# 03_-_28PINS_SCHEMATIC.net
KiCad netlist of a schematic drawn in Altium Designer
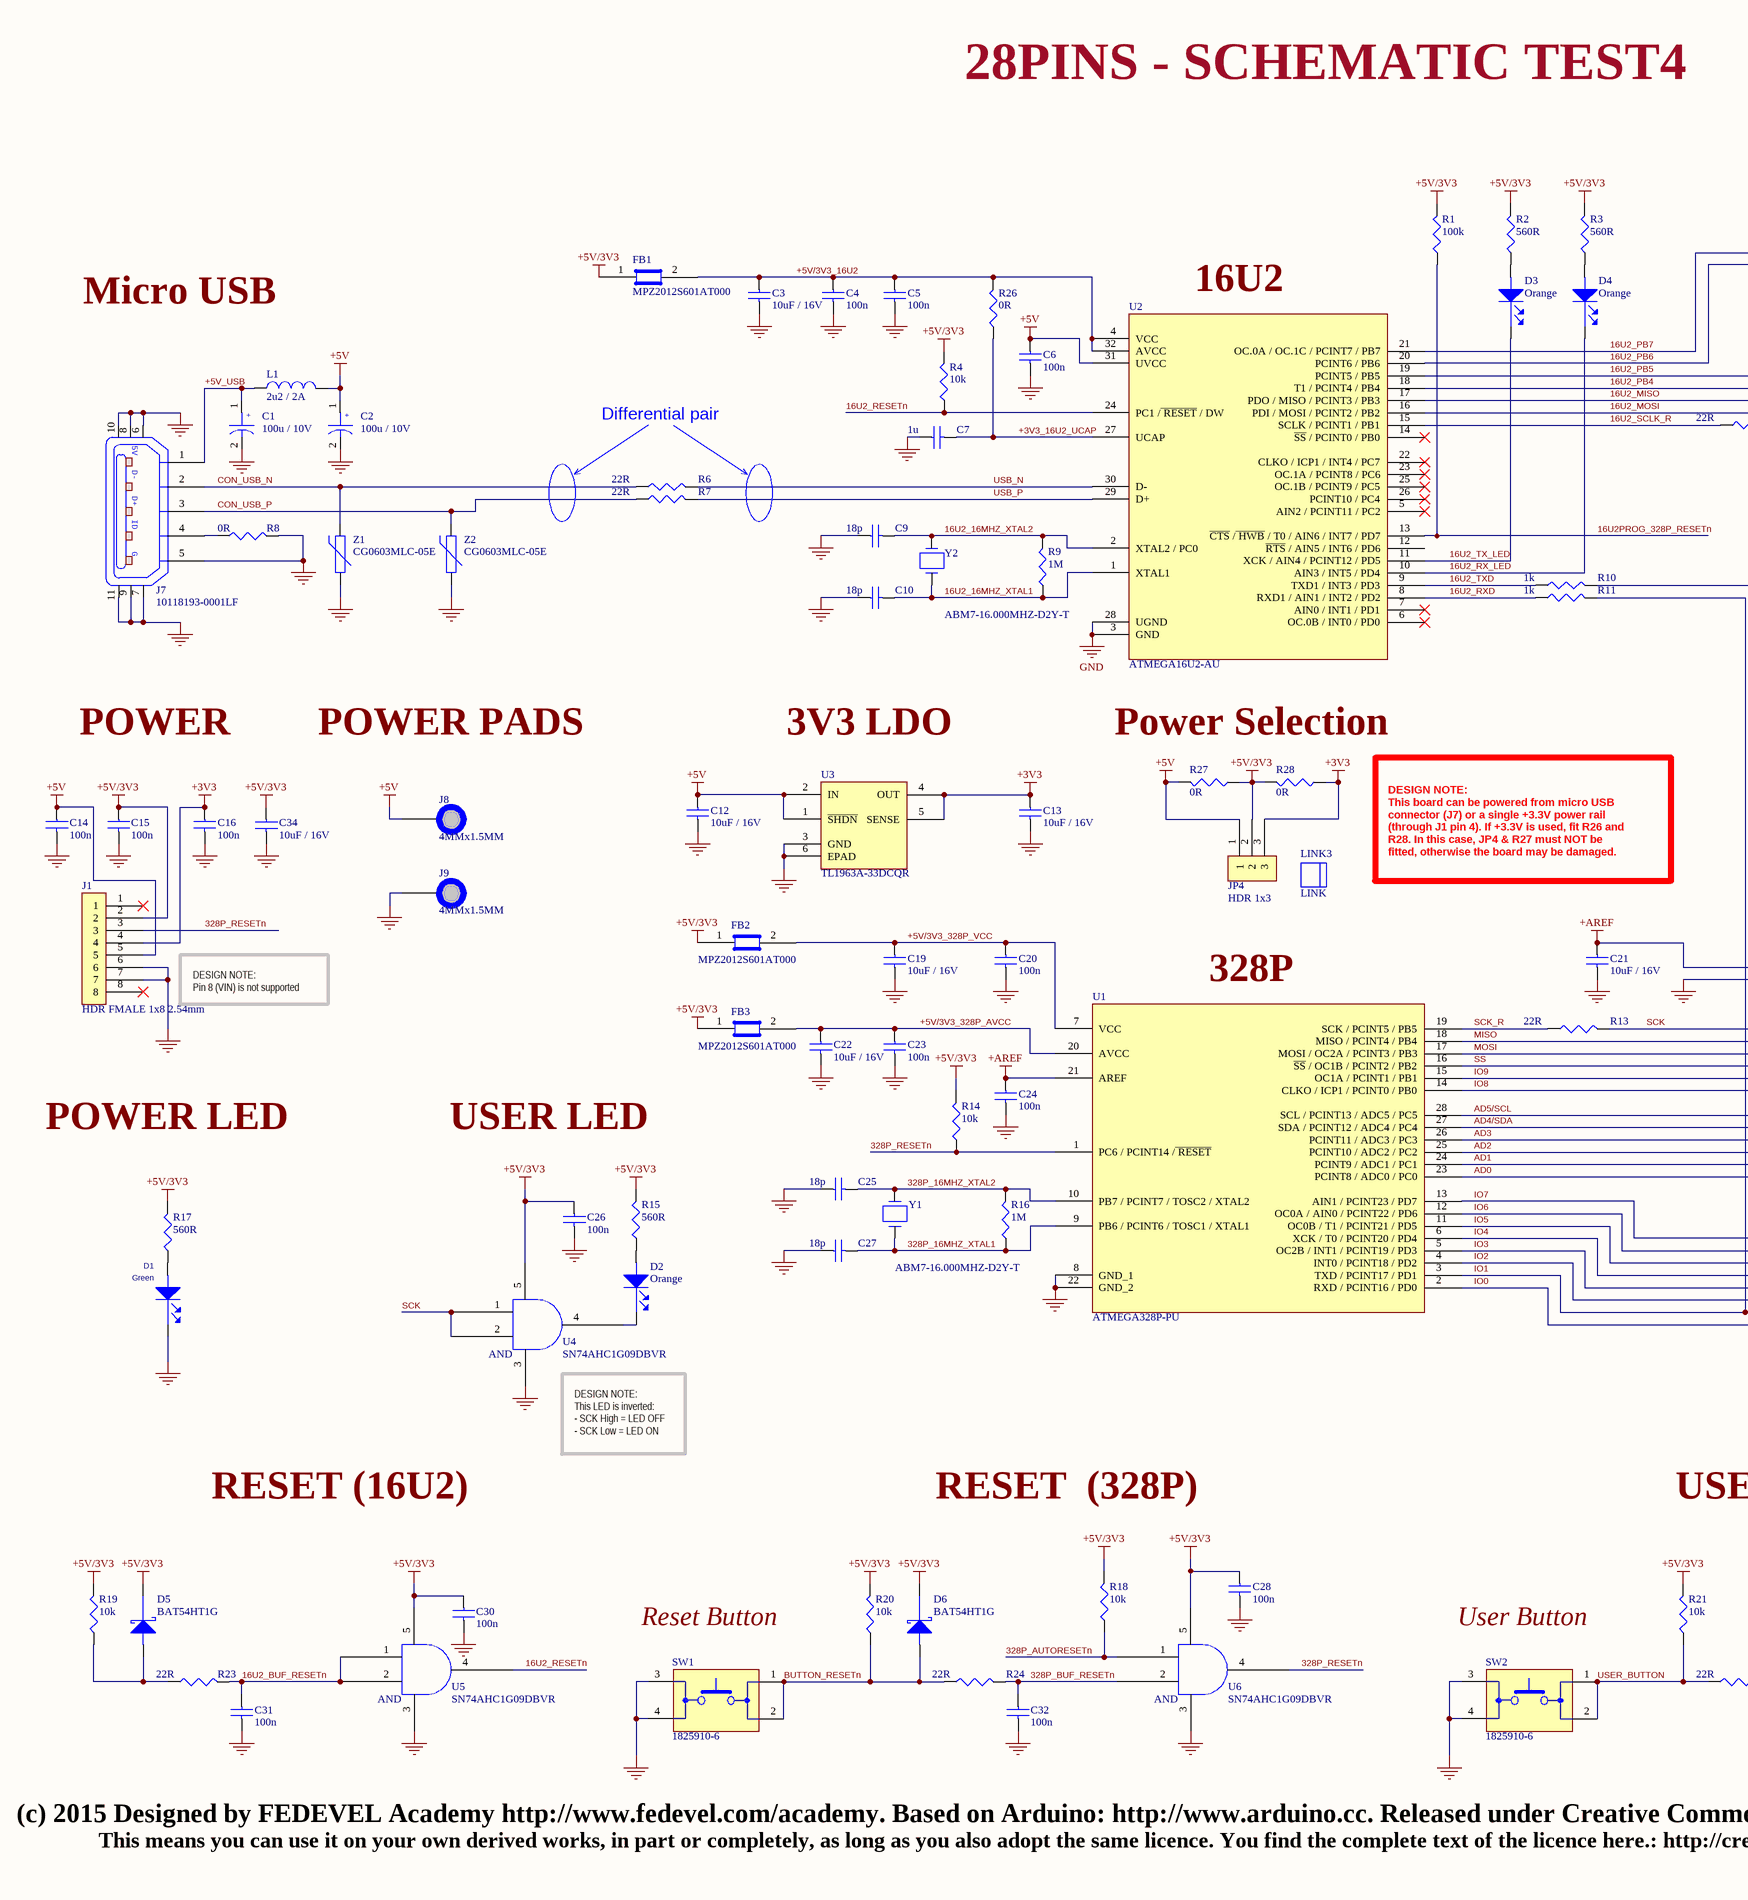
[diagram p0: [03] - 28PINS SCHEMATIC.SchDoc, left]
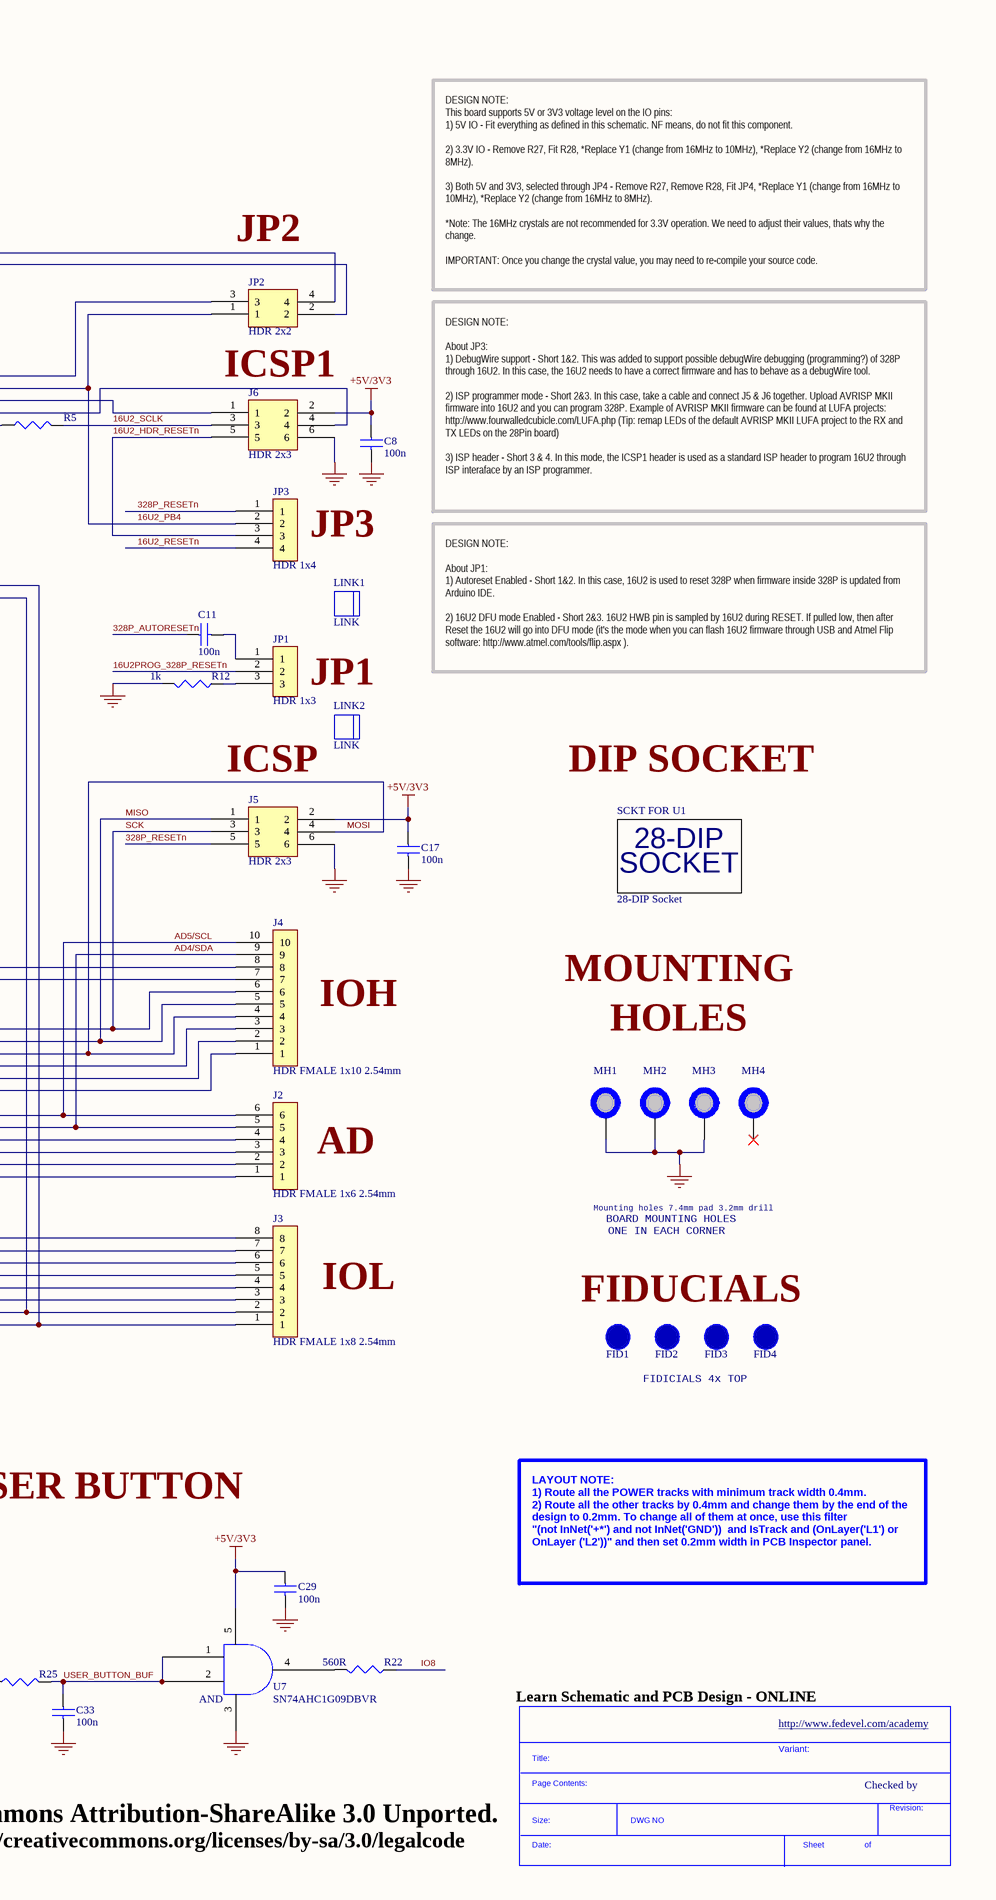
[diagram p1: [03] - 28PINS SCHEMATIC.SchDoc, right]

(export (version "E")
  (design (tool "Eeschema 10.0.6"))
  (components
    (comp (ref "*") (value "SDTitleBlock") (libsource (lib "*") (part "SDTitleBlock")))
    (comp (ref "C1")
      (value "100u / 10V")
      (footprint "C_ALU_C_SIZE")
      (description "CAP ALUM 100UF 10V 20% SMD")
      (fields
        (field (name "MANUFACTURER") "Panasonic Electronic Components")
        (field (name "MANUFACTURER PART NUMBER") "EEE-1AA101WR")
        (field (name ".CREATOR") "MM")
        (field (name ".CHECKED PCB") "RF")
        (field (name ".CHECKED SCH") "RF")
      )
      (libsource (lib "Integrated_Library_FEDEVEL_APR_2015") (part "EEE-1AA101WR"))
    )
    (comp (ref "C2")
      (value "100u / 10V")
      (footprint "C_ALU_C_SIZE")
      (description "CAP ALUM 100UF 10V 20% SMD")
      (fields
        (field (name "MANUFACTURER") "Panasonic Electronic Components")
        (field (name "MANUFACTURER PART NUMBER") "EEE-1AA101WR")
        (field (name ".CREATOR") "MM")
        (field (name ".CHECKED PCB") "RF")
        (field (name ".CHECKED SCH") "RF")
      )
      (libsource (lib "Integrated_Library_FEDEVEL_APR_2015") (part "EEE-1AA101WR"))
    )
    (comp (ref "C3")
      (value "10uF / 16V")
      (footprint "C0805")
      (description "CAP CER 10UF 16V 20% X5R 0805")
      (fields
        (field (name "MANUFACTURER") "TDK Corporation")
        (field (name "MANUFACTURER PART NUMBER") "C2012X5R1C106M/1.25")
      )
      (libsource (lib "Integrated_Library_FEDEVEL_APR_2015") (part "C2012X5R1C106M"))
    )
    (comp (ref "C4")
      (value "100n")
      (footprint "C0805")
      (description "CAP CER 0.1UF 50V 10% X7R 0805")
      (fields
        (field (name "MANUFACTURER") "TDK Corporation")
        (field (name "MANUFACTURER PART NUMBER") "C2012X7R1H104K085AA")
        (field (name ".CREATOR") "MM")
        (field (name ".CHECKED PCB") "RF")
        (field (name ".CHECKED SCH") "RF")
      )
      (libsource (lib "Integrated_Library_FEDEVEL_APR_2015") (part "C2012X7R1H104K085AA"))
    )
    (comp (ref "C5")
      (value "100n")
      (footprint "C0805")
      (description "CAP CER 0.1UF 50V 10% X7R 0805")
      (fields
        (field (name "MANUFACTURER") "TDK Corporation")
        (field (name "MANUFACTURER PART NUMBER") "C2012X7R1H104K085AA")
        (field (name ".CREATOR") "MM")
        (field (name ".CHECKED PCB") "RF")
        (field (name ".CHECKED SCH") "RF")
      )
      (libsource (lib "Integrated_Library_FEDEVEL_APR_2015") (part "C2012X7R1H104K085AA"))
    )
    (comp (ref "C6")
      (value "100n")
      (footprint "C0805")
      (description "CAP CER 0.1UF 50V 10% X7R 0805")
      (fields
        (field (name "MANUFACTURER") "TDK Corporation")
        (field (name "MANUFACTURER PART NUMBER") "C2012X7R1H104K085AA")
        (field (name ".CREATOR") "MM")
        (field (name ".CHECKED PCB") "RF")
        (field (name ".CHECKED SCH") "RF")
      )
      (libsource (lib "Integrated_Library_FEDEVEL_APR_2015") (part "C2012X7R1H104K085AA"))
    )
    (comp (ref "C7")
      (value "1u")
      (footprint "C0805")
      (description "CAP CER 1UF 25V 10% X5R 0805")
      (fields
        (field (name "MANUFACTURER") "TDK Corporation")
        (field (name "MANUFACTURER PART NUMBER") "C2012X5R1E105K125AA")
        (field (name ".CREATOR") "MM")
        (field (name ".CHECKED PCB") "RF")
        (field (name ".CHECKED SCH") "RF")
      )
      (libsource (lib "Integrated_Library_FEDEVEL_APR_2015") (part "C2012X5R1E105K125AA"))
    )
    (comp (ref "C8")
      (value "100n")
      (footprint "C0805")
      (description "CAP CER 0.1UF 50V 10% X7R 0805")
      (fields
        (field (name "MANUFACTURER") "TDK Corporation")
        (field (name "MANUFACTURER PART NUMBER") "C2012X7R1H104K085AA")
        (field (name ".CREATOR") "MM")
        (field (name ".CHECKED PCB") "RF")
        (field (name ".CHECKED SCH") "RF")
      )
      (libsource (lib "Integrated_Library_FEDEVEL_APR_2015") (part "C2012X7R1H104K085AA"))
    )
    (comp (ref "C9")
      (value "18p")
      (footprint "C0805")
      (description "CAP CER 18PF 50V 5% NP0 0805")
      (fields
        (field (name "MANUFACTURER") "Kemet")
        (field (name "MANUFACTURER PART NUMBER") "C0805C180J5GACTU")
        (field (name ".CREATOR") "MM")
        (field (name ".CHECKED PCB") "RF")
        (field (name ".CHECKED SCH") "RF")
      )
      (libsource (lib "Integrated_Library_FEDEVEL_APR_2015") (part "C0805C180J5GACTU"))
    )
    (comp (ref "C10")
      (value "18p")
      (footprint "C0805")
      (description "CAP CER 18PF 50V 5% NP0 0805")
      (fields
        (field (name "MANUFACTURER") "Kemet")
        (field (name "MANUFACTURER PART NUMBER") "C0805C180J5GACTU")
        (field (name ".CREATOR") "MM")
        (field (name ".CHECKED PCB") "RF")
        (field (name ".CHECKED SCH") "RF")
      )
      (libsource (lib "Integrated_Library_FEDEVEL_APR_2015") (part "C0805C180J5GACTU"))
    )
    (comp (ref "C11")
      (value "100n")
      (footprint "C0805")
      (description "CAP CER 0.1UF 50V 10% X7R 0805")
      (fields
        (field (name "MANUFACTURER") "TDK Corporation")
        (field (name "MANUFACTURER PART NUMBER") "C2012X7R1H104K085AA")
        (field (name ".CREATOR") "MM")
        (field (name ".CHECKED PCB") "RF")
        (field (name ".CHECKED SCH") "RF")
      )
      (libsource (lib "Integrated_Library_FEDEVEL_APR_2015") (part "C2012X7R1H104K085AA"))
    )
    (comp (ref "C12")
      (value "10uF / 16V")
      (footprint "C0805")
      (description "CAP CER 10UF 16V 20% X5R 0805")
      (fields
        (field (name "MANUFACTURER") "TDK Corporation")
        (field (name "MANUFACTURER PART NUMBER") "C2012X5R1C106M/1.25")
      )
      (libsource (lib "Integrated_Library_FEDEVEL_APR_2015") (part "C2012X5R1C106M"))
    )
    (comp (ref "C13")
      (value "10uF / 16V")
      (footprint "C0805")
      (description "CAP CER 10UF 16V 20% X5R 0805")
      (fields
        (field (name "MANUFACTURER") "TDK Corporation")
        (field (name "MANUFACTURER PART NUMBER") "C2012X5R1C106M/1.25")
      )
      (libsource (lib "Integrated_Library_FEDEVEL_APR_2015") (part "C2012X5R1C106M"))
    )
    (comp (ref "C14")
      (value "100n")
      (footprint "C0805")
      (description "CAP CER 0.1UF 50V 10% X7R 0805")
      (fields
        (field (name "MANUFACTURER") "TDK Corporation")
        (field (name "MANUFACTURER PART NUMBER") "C2012X7R1H104K085AA")
        (field (name ".CREATOR") "MM")
        (field (name ".CHECKED PCB") "RF")
        (field (name ".CHECKED SCH") "RF")
      )
      (libsource (lib "Integrated_Library_FEDEVEL_APR_2015") (part "C2012X7R1H104K085AA"))
    )
    (comp (ref "C15")
      (value "100n")
      (footprint "C0805")
      (description "CAP CER 0.1UF 50V 10% X7R 0805")
      (fields
        (field (name "MANUFACTURER") "TDK Corporation")
        (field (name "MANUFACTURER PART NUMBER") "C2012X7R1H104K085AA")
        (field (name ".CREATOR") "MM")
        (field (name ".CHECKED PCB") "RF")
        (field (name ".CHECKED SCH") "RF")
      )
      (libsource (lib "Integrated_Library_FEDEVEL_APR_2015") (part "C2012X7R1H104K085AA"))
    )
    (comp (ref "C16")
      (value "100n")
      (footprint "C0805")
      (description "CAP CER 0.1UF 50V 10% X7R 0805")
      (fields
        (field (name "MANUFACTURER") "TDK Corporation")
        (field (name "MANUFACTURER PART NUMBER") "C2012X7R1H104K085AA")
        (field (name ".CREATOR") "MM")
        (field (name ".CHECKED PCB") "RF")
        (field (name ".CHECKED SCH") "RF")
      )
      (libsource (lib "Integrated_Library_FEDEVEL_APR_2015") (part "C2012X7R1H104K085AA"))
    )
    (comp (ref "C17")
      (value "100n")
      (footprint "C0805")
      (description "CAP CER 0.1UF 50V 10% X7R 0805")
      (fields
        (field (name "MANUFACTURER") "TDK Corporation")
        (field (name "MANUFACTURER PART NUMBER") "C2012X7R1H104K085AA")
        (field (name ".CREATOR") "MM")
        (field (name ".CHECKED PCB") "RF")
        (field (name ".CHECKED SCH") "RF")
      )
      (libsource (lib "Integrated_Library_FEDEVEL_APR_2015") (part "C2012X7R1H104K085AA"))
    )
    (comp (ref "C19")
      (value "10uF / 16V")
      (footprint "C0805")
      (description "CAP CER 10UF 16V 20% X5R 0805")
      (fields
        (field (name "MANUFACTURER") "TDK Corporation")
        (field (name "MANUFACTURER PART NUMBER") "C2012X5R1C106M/1.25")
      )
      (libsource (lib "Integrated_Library_FEDEVEL_APR_2015") (part "C2012X5R1C106M"))
    )
    (comp (ref "C20")
      (value "100n")
      (footprint "C0805")
      (description "CAP CER 0.1UF 50V 10% X7R 0805")
      (fields
        (field (name "MANUFACTURER") "TDK Corporation")
        (field (name "MANUFACTURER PART NUMBER") "C2012X7R1H104K085AA")
        (field (name ".CREATOR") "MM")
        (field (name ".CHECKED PCB") "RF")
        (field (name ".CHECKED SCH") "RF")
      )
      (libsource (lib "Integrated_Library_FEDEVEL_APR_2015") (part "C2012X7R1H104K085AA"))
    )
    (comp (ref "C21")
      (value "10uF / 16V")
      (footprint "C0805")
      (description "CAP CER 10UF 16V 20% X5R 0805")
      (fields
        (field (name "MANUFACTURER") "TDK Corporation")
        (field (name "MANUFACTURER PART NUMBER") "C2012X5R1C106M/1.25")
      )
      (libsource (lib "Integrated_Library_FEDEVEL_APR_2015") (part "C2012X5R1C106M"))
    )
    (comp (ref "C22")
      (value "10uF / 16V")
      (footprint "C0805")
      (description "CAP CER 10UF 16V 20% X5R 0805")
      (fields
        (field (name "MANUFACTURER") "TDK Corporation")
        (field (name "MANUFACTURER PART NUMBER") "C2012X5R1C106M/1.25")
      )
      (libsource (lib "Integrated_Library_FEDEVEL_APR_2015") (part "C2012X5R1C106M"))
    )
    (comp (ref "C23")
      (value "100n")
      (footprint "C0805")
      (description "CAP CER 0.1UF 50V 10% X7R 0805")
      (fields
        (field (name "MANUFACTURER") "TDK Corporation")
        (field (name "MANUFACTURER PART NUMBER") "C2012X7R1H104K085AA")
        (field (name ".CREATOR") "MM")
        (field (name ".CHECKED PCB") "RF")
        (field (name ".CHECKED SCH") "RF")
      )
      (libsource (lib "Integrated_Library_FEDEVEL_APR_2015") (part "C2012X7R1H104K085AA"))
    )
    (comp (ref "C24")
      (value "100n")
      (footprint "C0805")
      (description "CAP CER 0.1UF 50V 10% X7R 0805")
      (fields
        (field (name "MANUFACTURER") "TDK Corporation")
        (field (name "MANUFACTURER PART NUMBER") "C2012X7R1H104K085AA")
        (field (name ".CREATOR") "MM")
        (field (name ".CHECKED PCB") "RF")
        (field (name ".CHECKED SCH") "RF")
      )
      (libsource (lib "Integrated_Library_FEDEVEL_APR_2015") (part "C2012X7R1H104K085AA"))
    )
    (comp (ref "C25")
      (value "18p")
      (footprint "C0805")
      (description "CAP CER 18PF 50V 5% NP0 0805")
      (fields
        (field (name "MANUFACTURER") "Kemet")
        (field (name "MANUFACTURER PART NUMBER") "C0805C180J5GACTU")
        (field (name ".CREATOR") "MM")
        (field (name ".CHECKED PCB") "RF")
        (field (name ".CHECKED SCH") "RF")
      )
      (libsource (lib "Integrated_Library_FEDEVEL_APR_2015") (part "C0805C180J5GACTU"))
    )
    (comp (ref "C26")
      (value "100n")
      (footprint "C0805")
      (description "CAP CER 0.1UF 50V 10% X7R 0805")
      (fields
        (field (name "MANUFACTURER") "TDK Corporation")
        (field (name "MANUFACTURER PART NUMBER") "C2012X7R1H104K085AA")
        (field (name ".CREATOR") "MM")
        (field (name ".CHECKED PCB") "RF")
        (field (name ".CHECKED SCH") "RF")
      )
      (libsource (lib "Integrated_Library_FEDEVEL_APR_2015") (part "C2012X7R1H104K085AA"))
    )
    (comp (ref "C27")
      (value "18p")
      (footprint "C0805")
      (description "CAP CER 18PF 50V 5% NP0 0805")
      (fields
        (field (name "MANUFACTURER") "Kemet")
        (field (name "MANUFACTURER PART NUMBER") "C0805C180J5GACTU")
        (field (name ".CREATOR") "MM")
        (field (name ".CHECKED PCB") "RF")
        (field (name ".CHECKED SCH") "RF")
      )
      (libsource (lib "Integrated_Library_FEDEVEL_APR_2015") (part "C0805C180J5GACTU"))
    )
    (comp (ref "C28")
      (value "100n")
      (footprint "C0805")
      (description "CAP CER 0.1UF 50V 10% X7R 0805")
      (fields
        (field (name "MANUFACTURER") "TDK Corporation")
        (field (name "MANUFACTURER PART NUMBER") "C2012X7R1H104K085AA")
        (field (name ".CREATOR") "MM")
        (field (name ".CHECKED PCB") "RF")
        (field (name ".CHECKED SCH") "RF")
      )
      (libsource (lib "Integrated_Library_FEDEVEL_APR_2015") (part "C2012X7R1H104K085AA"))
    )
    (comp (ref "C29")
      (value "100n")
      (footprint "C0805")
      (description "CAP CER 0.1UF 50V 10% X7R 0805")
      (fields
        (field (name "MANUFACTURER") "TDK Corporation")
        (field (name "MANUFACTURER PART NUMBER") "C2012X7R1H104K085AA")
        (field (name ".CREATOR") "MM")
        (field (name ".CHECKED PCB") "RF")
        (field (name ".CHECKED SCH") "RF")
      )
      (libsource (lib "Integrated_Library_FEDEVEL_APR_2015") (part "C2012X7R1H104K085AA"))
    )
    (comp (ref "C30")
      (value "100n")
      (footprint "C0805")
      (description "CAP CER 0.1UF 50V 10% X7R 0805")
      (fields
        (field (name "MANUFACTURER") "TDK Corporation")
        (field (name "MANUFACTURER PART NUMBER") "C2012X7R1H104K085AA")
        (field (name ".CREATOR") "MM")
        (field (name ".CHECKED PCB") "RF")
        (field (name ".CHECKED SCH") "RF")
      )
      (libsource (lib "Integrated_Library_FEDEVEL_APR_2015") (part "C2012X7R1H104K085AA"))
    )
    (comp (ref "C31")
      (value "100n")
      (footprint "C0805")
      (description "CAP CER 0.1UF 50V 10% X7R 0805")
      (fields
        (field (name "MANUFACTURER") "TDK Corporation")
        (field (name "MANUFACTURER PART NUMBER") "C2012X7R1H104K085AA")
        (field (name ".CREATOR") "MM")
        (field (name ".CHECKED PCB") "RF")
        (field (name ".CHECKED SCH") "RF")
      )
      (libsource (lib "Integrated_Library_FEDEVEL_APR_2015") (part "C2012X7R1H104K085AA"))
    )
    (comp (ref "C32")
      (value "100n")
      (footprint "C0805")
      (description "CAP CER 0.1UF 50V 10% X7R 0805")
      (fields
        (field (name "MANUFACTURER") "TDK Corporation")
        (field (name "MANUFACTURER PART NUMBER") "C2012X7R1H104K085AA")
        (field (name ".CREATOR") "MM")
        (field (name ".CHECKED PCB") "RF")
        (field (name ".CHECKED SCH") "RF")
      )
      (libsource (lib "Integrated_Library_FEDEVEL_APR_2015") (part "C2012X7R1H104K085AA"))
    )
    (comp (ref "C33")
      (value "100n")
      (footprint "C0805")
      (description "CAP CER 0.1UF 50V 10% X7R 0805")
      (fields
        (field (name "MANUFACTURER") "TDK Corporation")
        (field (name "MANUFACTURER PART NUMBER") "C2012X7R1H104K085AA")
        (field (name ".CREATOR") "MM")
        (field (name ".CHECKED PCB") "RF")
        (field (name ".CHECKED SCH") "RF")
      )
      (libsource (lib "Integrated_Library_FEDEVEL_APR_2015") (part "C2012X7R1H104K085AA"))
    )
    (comp (ref "C34")
      (value "10uF / 16V")
      (footprint "C0805")
      (description "CAP CER 10UF 16V 20% X5R 0805")
      (fields
        (field (name "MANUFACTURER") "TDK Corporation")
        (field (name "MANUFACTURER PART NUMBER") "C2012X5R1C106M/1.25")
      )
      (libsource (lib "Integrated_Library_FEDEVEL_APR_2015") (part "C2012X5R1C106M"))
    )
    (comp (ref "D1")
      (value "Green")
      (footprint "LED_0603")
      (description "LED SMARTLED GREEN 570NM 0603")
      (fields
        (field (name "MANUFACTURER") "OSRAM Opto Semiconductors Inc")
        (field (name "MANUFACTURER PART NUMBER") "LG L29K-G2J1-24-Z")
      )
      (libsource (lib "Integrated_Library_FEDEVEL_APR_2015") (part "LG L29K-G2J1-24-Z"))
    )
    (comp (ref "D2")
      (value "Orange")
      (footprint "LED_0603")
      (description "LED SMARTLED ORANGE 606NM 0603")
      (fields
        (field (name "MANUFACTURER") "OSRAM Opto Semiconductors Inc")
        (field (name "MANUFACTURER PART NUMBER") "LO L29K-H2K1-24-Z")
      )
      (libsource (lib "Integrated_Library_FEDEVEL_APR_2015") (part "LO L29K-H2K1-24-Z"))
    )
    (comp (ref "D3")
      (value "Orange")
      (footprint "LED_0603")
      (description "LED SMARTLED ORANGE 606NM 0603")
      (fields
        (field (name "MANUFACTURER") "OSRAM Opto Semiconductors Inc")
        (field (name "MANUFACTURER PART NUMBER") "LO L29K-H2K1-24-Z")
      )
      (libsource (lib "Integrated_Library_FEDEVEL_APR_2015") (part "LO L29K-H2K1-24-Z"))
    )
    (comp (ref "D4")
      (value "Orange")
      (footprint "LED_0603")
      (description "LED SMARTLED ORANGE 606NM 0603")
      (fields
        (field (name "MANUFACTURER") "OSRAM Opto Semiconductors Inc")
        (field (name "MANUFACTURER PART NUMBER") "LO L29K-H2K1-24-Z")
      )
      (libsource (lib "Integrated_Library_FEDEVEL_APR_2015") (part "LO L29K-H2K1-24-Z"))
    )
    (comp (ref "D5")
      (value "BAT54HT1G")
      (footprint "SOD323")
      (description "DIODE SCHOTTKY 30V 0.2A SOD323")
      (fields (field (name "MANUFACTURER") "Fairchild Semiconductor") (field (name ".CREATOR") "MM"))
      (libsource (lib "Integrated_Library_FEDEVEL_APR_2015") (part "BAT54HT1G"))
    )
    (comp (ref "D6")
      (value "BAT54HT1G")
      (footprint "SOD323")
      (description "DIODE SCHOTTKY 30V 0.2A SOD323")
      (fields (field (name "MANUFACTURER") "Fairchild Semiconductor") (field (name ".CREATOR") "MM"))
      (libsource (lib "Integrated_Library_FEDEVEL_APR_2015") (part "BAT54HT1G"))
    )
    (comp (ref "FB1")
      (value "MPZ2012S601AT000")
      (footprint "C0805")
      (description "FERRITE CHIP BEAD 600 OHM SMD")
      (fields
        (field (name "MANUFACTURER") "TDK Corporation")
        (field (name ".CREATOR") "MM")
        (field (name ".CHECKED PCB") "RF")
        (field (name ".CHECKED SCH") "RF")
      )
      (libsource (lib "Integrated_Library_FEDEVEL_APR_2015") (part "MPZ2012S601AT000"))
    )
    (comp (ref "FB2")
      (value "MPZ2012S601AT000")
      (footprint "C0805")
      (description "FERRITE CHIP BEAD 600 OHM SMD")
      (fields
        (field (name "MANUFACTURER") "TDK Corporation")
        (field (name ".CREATOR") "MM")
        (field (name ".CHECKED PCB") "RF")
        (field (name ".CHECKED SCH") "RF")
      )
      (libsource (lib "Integrated_Library_FEDEVEL_APR_2015") (part "MPZ2012S601AT000"))
    )
    (comp (ref "FB3")
      (value "MPZ2012S601AT000")
      (footprint "C0805")
      (description "FERRITE CHIP BEAD 600 OHM SMD")
      (fields
        (field (name "MANUFACTURER") "TDK Corporation")
        (field (name ".CREATOR") "MM")
        (field (name ".CHECKED PCB") "RF")
        (field (name ".CHECKED SCH") "RF")
      )
      (libsource (lib "Integrated_Library_FEDEVEL_APR_2015") (part "MPZ2012S601AT000"))
    )
    (comp (ref "FID1")
      (value "FID_1MMC")
      (footprint "FID_40X120D")
      (description "Fiducial 40mil Diameter, 120mil Mask")
      (libsource (lib "Integrated_Library_FEDEVEL_APR_2015") (part "FID_1MMC"))
    )
    (comp (ref "FID2")
      (value "FID_1MMC")
      (footprint "FID_40X120D")
      (description "Fiducial 40mil Diameter, 120mil Mask")
      (libsource (lib "Integrated_Library_FEDEVEL_APR_2015") (part "FID_1MMC"))
    )
    (comp (ref "FID3")
      (value "FID_1MMC")
      (footprint "FID_40X120D")
      (description "Fiducial 40mil Diameter, 120mil Mask")
      (libsource (lib "Integrated_Library_FEDEVEL_APR_2015") (part "FID_1MMC"))
    )
    (comp (ref "FID4")
      (value "FID_1MMC")
      (footprint "FID_40X120D")
      (description "Fiducial 40mil Diameter, 120mil Mask")
      (libsource (lib "Integrated_Library_FEDEVEL_APR_2015") (part "FID_1MMC"))
    )
    (comp (ref "J1")
      (value "HDR FMALE 1x8 2.54mm")
      (footprint "Hdr_Female_1x8_2.54mm")
      (description "08-WAY SIL VERT SOCKET L/FREE")
      (fields
        (field (name "MANUFACTURER") "Harwin Inc")
        (field (name "MANUFACTURER PART NUMBER") "M20-7820842")
        (field (name ".CREATOR") "MM")
        (field (name ".CHECKED PCB") "RF")
        (field (name ".CHECKED SCH") "RF")
      )
      (libsource (lib "Integrated_Library_FEDEVEL_APR_2015") (part "M20-7820842"))
    )
    (comp (ref "J2")
      (value "HDR FMALE 1x6 2.54mm")
      (footprint "Hdr_Female_1x6_2.54mm")
      (description "06-WAY SIL VERT SOCKET L/FREE")
      (fields
        (field (name "MANUFACTURER") "Harwin Inc")
        (field (name "MANUFACTURER PART NUMBER") "M20-7820646")
        (field (name ".CHECKED PCB") "MM")
        (field (name ".CHECKED SCH") "MM")
        (field (name ".CREATOR") "MM")
      )
      (libsource (lib "Integrated_Library_FEDEVEL_APR_2015") (part "M20-7820646"))
    )
    (comp (ref "J3")
      (value "HDR FMALE 1x8 2.54mm")
      (footprint "Hdr_Female_1x8_2.54mm")
      (description "08-WAY SIL VERT SOCKET L/FREE")
      (fields
        (field (name "MANUFACTURER") "Harwin Inc")
        (field (name "MANUFACTURER PART NUMBER") "M20-7820842")
        (field (name ".CREATOR") "MM")
        (field (name ".CHECKED PCB") "RF")
        (field (name ".CHECKED SCH") "RF")
      )
      (libsource (lib "") (part "M20-7820842_1"))
    )
    (comp (ref "J4")
      (value "HDR FMALE 1x10 2.54mm")
      (footprint "Hdr_Female_1x10_2.54mm")
      (description "10-WAY SIL VERT SOCKET L/FREE")
      (fields
        (field (name "MANUFACTURER") "Harwin Inc")
        (field (name "MANUFACTURER PART NUMBER") "M20-7821046")
        (field (name ".CREATOR") "MM")
        (field (name ".CHECKED PCB") "RF")
        (field (name ".CHECKED SCH") "RF")
      )
      (libsource (lib "Integrated_Library_FEDEVEL_APR_2015") (part "M20-7821046"))
    )
    (comp (ref "J5")
      (value "HDR 2x3")
      (footprint "HDR_2x3_2.54MM")
      (description "CONN HEADER 6POS .100 STR 30AU")
      (fields
        (field (name "MANUFACTURER") "FCI")
        (field (name "MANUFACTURER PART NUMBER") "67997-106HLF")
        (field (name ".CREATOR") "MM")
        (field (name ".CHECKED PCB") "RF")
        (field (name ".CHECKED SCH") "RF")
      )
      (libsource (lib "Integrated_Library_FEDEVEL_APR_2015") (part "67997-106HLF"))
    )
    (comp (ref "J6")
      (value "HDR 2x3")
      (footprint "HDR_2x3_2.54MM")
      (description "CONN HEADER 6POS .100 STR 30AU")
      (fields
        (field (name "MANUFACTURER") "FCI")
        (field (name "MANUFACTURER PART NUMBER") "67997-106HLF")
        (field (name ".CREATOR") "MM")
        (field (name ".CHECKED PCB") "RF")
        (field (name ".CHECKED SCH") "RF")
      )
      (libsource (lib "Integrated_Library_FEDEVEL_APR_2015") (part "67997-106HLF"))
    )
    (comp (ref "J7")
      (value "10118193-0001LF")
      (footprint "10118193")
      (description "CONN USB MICRO B RECPT SMT R/A")
      (fields
        (field (name "MANUFACTURER") "FCI")
        (field (name ".CREATOR") "MM")
        (field (name ".CHECKED PCB") "RF")
        (field (name ".CHECKED SCH") "MM")
      )
      (libsource (lib "Integrated_Library_FEDEVEL_APR_2015") (part "10118193-0001LF"))
    )
    (comp (ref "J8")
      (value "4MMx1.5MM")
      (footprint "PAD_WITH_HOLE_4MMx1.5MM")
      (description "Pad with a hole 4mm x 1.5mm")
      (libsource (lib "Integrated_Library_FEDEVEL_APR_2015") (part "PAD_WITH_HOLE_4MMx1.5MM"))
    )
    (comp (ref "J9")
      (value "4MMx1.5MM")
      (footprint "PAD_WITH_HOLE_4MMx1.5MM")
      (description "Pad with a hole 4mm x 1.5mm")
      (libsource (lib "Integrated_Library_FEDEVEL_APR_2015") (part "PAD_WITH_HOLE_4MMx1.5MM"))
    )
    (comp (ref "JP1")
      (value "HDR 1x3")
      (footprint "Hdr_1x3_2.54mm")
      (description "BERGSTIK II .100\" SR STRAIGHT")
      (fields
        (field (name "MANUFACTURER") "FCI")
        (field (name "MANUFACTURER PART NUMBER") "68000-103HLF")
        (field (name ".CREATOR") "MM")
      )
      (libsource (lib "Integrated_Library_FEDEVEL_APR_2015") (part "68000-103HLF"))
    )
    (comp (ref "JP2")
      (value "HDR 2x2")
      (footprint "HDR_2x2_2.54MM")
      (description "CONN HEADER 4POS .100 STR 15AU")
      (fields
        (field (name "MANUFACTURER") "FCI")
        (field (name "MANUFACTURER PART NUMBER") "68602-204HLF")
        (field (name ".CREATOR") "MM")
        (field (name ".CHECKED PCB") "RF")
        (field (name ".CHECKED SCH") "RF")
      )
      (libsource (lib "Integrated_Library_FEDEVEL_APR_2015") (part "68602-204HLF"))
    )
    (comp (ref "JP3")
      (value "HDR 1x4")
      (footprint "HDR_1x4_2.54MM")
      (description "CONN HEADER 4POS .100 STR 15AU")
      (fields
        (field (name "MANUFACTURER") "FCI")
        (field (name "MANUFACTURER PART NUMBER") "68001-204HLF")
        (field (name ".CHECKED PCB") "RF")
        (field (name ".CHECKED SCH") "RF")
      )
      (libsource (lib "Integrated_Library_FEDEVEL_APR_2015") (part "68001-204HLF"))
    )
    (comp (ref "JP4")
      (value "HDR 1x3")
      (footprint "Hdr_1x3_2.54mm")
      (description "BERGSTIK II .100\" SR STRAIGHT")
      (fields
        (field (name "MANUFACTURER") "FCI")
        (field (name "MANUFACTURER PART NUMBER") "68000-103HLF")
        (field (name ".CREATOR") "MM")
      )
      (libsource (lib "") (part "68000-103HLF_1"))
    )
    (comp (ref "L1")
      (value "2u2 / 2A")
      (footprint "C1210_IND")
      (description "FIXED IND 2.2UH 2A 80 MOHM SMD")
      (fields
        (field (name "MANUFACTURER") "Kemet")
        (field (name "MANUFACTURER PART NUMBER") "L1210R2R2MDWIT")
        (field (name ".CREATOR") "MM")
        (field (name ".CHECKED PCB") "RF")
        (field (name ".CHECKED SCH") "RF")
      )
      (libsource (lib "Integrated_Library_FEDEVEL_APR_2015") (part "L1210R2R2MDWIT"))
    )
    (comp (ref "LINK1")
      (value "LINK")
      (description "CONN JUMPER SHORTING .100\" GOLD")
      (fields
        (field (name "MANUFACTURER") "Sullins Connector Solutions")
        (field (name "MANUFACTURER PART NUMBER") "QPC02SXGN-RC")
      )
      (libsource (lib "Integrated_Library_FEDEVEL_APR_2015") (part "QPC02SXGN-RC"))
    )
    (comp (ref "LINK2")
      (value "LINK")
      (description "CONN JUMPER SHORTING .100\" GOLD")
      (fields
        (field (name "MANUFACTURER") "Sullins Connector Solutions")
        (field (name "MANUFACTURER PART NUMBER") "QPC02SXGN-RC")
      )
      (libsource (lib "Integrated_Library_FEDEVEL_APR_2015") (part "QPC02SXGN-RC"))
    )
    (comp (ref "LINK3")
      (value "LINK")
      (description "CONN JUMPER SHORTING .100\" GOLD")
      (fields
        (field (name "MANUFACTURER") "Sullins Connector Solutions")
        (field (name "MANUFACTURER PART NUMBER") "QPC02SXGN-RC")
      )
      (libsource (lib "Integrated_Library_FEDEVEL_APR_2015") (part "QPC02SXGN-RC"))
    )
    (comp (ref "MH1")
      (value "MH_7.4MMC_3.2MMD")
      (footprint "MH_7.4MMD_3.2MMD")
      (description "Mounting Hole 7.4mm Diameter, 3.2mm Drill")
      (fields (field (name ".CREATOR") "MM"))
      (libsource (lib "Integrated_Library_FEDEVEL_APR_2015") (part "MH_7.4MMC_3.2MMD"))
    )
    (comp (ref "MH2")
      (value "MH_7.4MMC_3.2MMD")
      (footprint "MH_7.4MMD_3.2MMD")
      (description "Mounting Hole 7.4mm Diameter, 3.2mm Drill")
      (fields (field (name ".CREATOR") "MM"))
      (libsource (lib "Integrated_Library_FEDEVEL_APR_2015") (part "MH_7.4MMC_3.2MMD"))
    )
    (comp (ref "MH3")
      (value "MH_7.4MMC_3.2MMD")
      (footprint "MH_7.4MMD_3.2MMD")
      (description "Mounting Hole 7.4mm Diameter, 3.2mm Drill")
      (fields (field (name ".CREATOR") "MM"))
      (libsource (lib "Integrated_Library_FEDEVEL_APR_2015") (part "MH_7.4MMC_3.2MMD"))
    )
    (comp (ref "MH4")
      (value "MH_7.4MMNC_3.2MMD")
      (footprint "MH_7.4MMD_3.2MMD_NON_COPPER_NPTH")
      (description "Mounting Hole 7.4mm Diameter (Non Copper), 3.2mm Drill NPTH")
      (libsource (lib "Integrated_Library_FEDEVEL_APR_2015") (part "MH_7.4MMNC_3.2MMD"))
    )
    (comp (ref "R1")
      (value "100k")
      (footprint "R0805")
      (description "RES SMD 100K OHM 1% 1/8W 0805")
      (fields
        (field (name "MANUFACTURER") "Yageo")
        (field (name "MANUFACTURER PART NUMBER") "RC0805FR-07100KL")
        (field (name ".CREATOR") "MM")
        (field (name ".CHECKED PCB") "RF")
        (field (name ".CHECKED SCH") "RF")
      )
      (libsource (lib "Integrated_Library_FEDEVEL_APR_2015") (part "RC0805FR-07100KL"))
    )
    (comp (ref "R2")
      (value "560R")
      (footprint "R0805")
      (description "RES SMD 560 OHM 1% 1/8W 0805")
      (fields
        (field (name "MANUFACTURER") "Yageo")
        (field (name "MANUFACTURER PART NUMBER") "RC0805FR-07560RL")
        (field (name ".CREATOR") "MM")
        (field (name ".CHECKED PCB") "RF")
        (field (name ".CHECKED SCH") "RF")
      )
      (libsource (lib "Integrated_Library_FEDEVEL_APR_2015") (part "RC0805FR-07560RL"))
    )
    (comp (ref "R3")
      (value "560R")
      (footprint "R0805")
      (description "RES SMD 560 OHM 1% 1/8W 0805")
      (fields
        (field (name "MANUFACTURER") "Yageo")
        (field (name "MANUFACTURER PART NUMBER") "RC0805FR-07560RL")
        (field (name ".CREATOR") "MM")
        (field (name ".CHECKED PCB") "RF")
        (field (name ".CHECKED SCH") "RF")
      )
      (libsource (lib "Integrated_Library_FEDEVEL_APR_2015") (part "RC0805FR-07560RL"))
    )
    (comp (ref "R4")
      (value "10k")
      (footprint "R0805")
      (description "RES SMD 10K OHM 1% 1/8W 0805")
      (fields
        (field (name "MANUFACTURER") "Yageo")
        (field (name "MANUFACTURER PART NUMBER") "RC0805FR-0710KL")
        (field (name ".CREATOR") "MM")
        (field (name ".CHECKED PCB") "RF")
        (field (name ".CHECKED SCH") "RF")
      )
      (libsource (lib "Integrated_Library_FEDEVEL_APR_2015") (part "RC0805FR-0710KL"))
    )
    (comp (ref "R5")
      (value "22R")
      (footprint "R0805")
      (description "RES SMD 22 OHM 1% 1/8W 0805")
      (fields
        (field (name "MANUFACTURER") "Yageo")
        (field (name "MANUFACTURER PART NUMBER") "RC0805FR-0722RL")
        (field (name ".CREATOR") "MM")
        (field (name ".CHECKED PCB") "RF")
        (field (name ".CHECKED SCH") "RF")
      )
      (libsource (lib "Integrated_Library_FEDEVEL_APR_2015") (part "RC0805FR-0722RL"))
    )
    (comp (ref "R6")
      (value "22R")
      (footprint "R0805")
      (description "RES SMD 22 OHM 1% 1/8W 0805")
      (fields
        (field (name "MANUFACTURER") "Yageo")
        (field (name "MANUFACTURER PART NUMBER") "RC0805FR-0722RL")
        (field (name ".CREATOR") "MM")
        (field (name ".CHECKED PCB") "RF")
        (field (name ".CHECKED SCH") "RF")
      )
      (libsource (lib "Integrated_Library_FEDEVEL_APR_2015") (part "RC0805FR-0722RL"))
    )
    (comp (ref "R7")
      (value "22R")
      (footprint "R0805")
      (description "RES SMD 22 OHM 1% 1/8W 0805")
      (fields
        (field (name "MANUFACTURER") "Yageo")
        (field (name "MANUFACTURER PART NUMBER") "RC0805FR-0722RL")
        (field (name ".CREATOR") "MM")
        (field (name ".CHECKED PCB") "RF")
        (field (name ".CHECKED SCH") "RF")
      )
      (libsource (lib "Integrated_Library_FEDEVEL_APR_2015") (part "RC0805FR-0722RL"))
    )
    (comp (ref "R8")
      (value "0R")
      (footprint "R0805")
      (description "RES 0.0 OHM 1/8W 0805 SMD")
      (fields
        (field (name "MANUFACTURER") "Yageo")
        (field (name "MANUFACTURER PART NUMBER") "RC0805JR-070RL")
        (field (name ".CHECKED PCB") "RF")
        (field (name ".CHECKED SCH") "RF")
      )
      (libsource (lib "Integrated_Library_FEDEVEL_APR_2015") (part "RC0805JR-070RL"))
    )
    (comp (ref "R9")
      (value "1M")
      (footprint "R0805")
      (description "RES SMD 1M OHM 1% 1/8W 0805")
      (fields
        (field (name "MANUFACTURER") "Yageo")
        (field (name "MANUFACTURER PART NUMBER") "RC0805FR-071ML")
        (field (name ".CREATOR") "MM")
        (field (name ".CHECKED PCB") "RF")
        (field (name ".CHECKED SCH") "RF")
      )
      (libsource (lib "Integrated_Library_FEDEVEL_APR_2015") (part "RC0805FR-071ML"))
    )
    (comp (ref "R10")
      (value "1k")
      (footprint "R0805")
      (description "RES SMD 1K OHM 1% 1/8W 0805")
      (fields
        (field (name "MANUFACTURER") "Yageo")
        (field (name "MANUFACTURER PART NUMBER") "RC0805FR-071KL")
        (field (name ".CREATOR") "MM")
        (field (name ".CHECKED PCB") "RF")
        (field (name ".CHECKED SCH") "RF")
      )
      (libsource (lib "Integrated_Library_FEDEVEL_APR_2015") (part "RC0805FR-071KL"))
    )
    (comp (ref "R11")
      (value "1k")
      (footprint "R0805")
      (description "RES SMD 1K OHM 1% 1/8W 0805")
      (fields
        (field (name "MANUFACTURER") "Yageo")
        (field (name "MANUFACTURER PART NUMBER") "RC0805FR-071KL")
        (field (name ".CREATOR") "MM")
        (field (name ".CHECKED PCB") "RF")
        (field (name ".CHECKED SCH") "RF")
      )
      (libsource (lib "Integrated_Library_FEDEVEL_APR_2015") (part "RC0805FR-071KL"))
    )
    (comp (ref "R12")
      (value "1k")
      (footprint "R0805")
      (description "RES SMD 1K OHM 1% 1/8W 0805")
      (fields
        (field (name "MANUFACTURER") "Yageo")
        (field (name "MANUFACTURER PART NUMBER") "RC0805FR-071KL")
        (field (name ".CREATOR") "MM")
        (field (name ".CHECKED PCB") "RF")
        (field (name ".CHECKED SCH") "RF")
      )
      (libsource (lib "Integrated_Library_FEDEVEL_APR_2015") (part "RC0805FR-071KL"))
    )
    (comp (ref "R13")
      (value "22R")
      (footprint "R0805")
      (description "RES SMD 22 OHM 1% 1/8W 0805")
      (fields
        (field (name "MANUFACTURER") "Yageo")
        (field (name "MANUFACTURER PART NUMBER") "RC0805FR-0722RL")
        (field (name ".CREATOR") "MM")
        (field (name ".CHECKED PCB") "RF")
        (field (name ".CHECKED SCH") "RF")
      )
      (libsource (lib "Integrated_Library_FEDEVEL_APR_2015") (part "RC0805FR-0722RL"))
    )
    (comp (ref "R14")
      (value "10k")
      (footprint "R0805")
      (description "RES SMD 10K OHM 1% 1/8W 0805")
      (fields
        (field (name "MANUFACTURER") "Yageo")
        (field (name "MANUFACTURER PART NUMBER") "RC0805FR-0710KL")
        (field (name ".CREATOR") "MM")
        (field (name ".CHECKED PCB") "RF")
        (field (name ".CHECKED SCH") "RF")
      )
      (libsource (lib "Integrated_Library_FEDEVEL_APR_2015") (part "RC0805FR-0710KL"))
    )
    (comp (ref "R15")
      (value "560R")
      (footprint "R0805")
      (description "RES SMD 560 OHM 1% 1/8W 0805")
      (fields
        (field (name "MANUFACTURER") "Yageo")
        (field (name "MANUFACTURER PART NUMBER") "RC0805FR-07560RL")
        (field (name ".CREATOR") "MM")
        (field (name ".CHECKED PCB") "RF")
        (field (name ".CHECKED SCH") "RF")
      )
      (libsource (lib "Integrated_Library_FEDEVEL_APR_2015") (part "RC0805FR-07560RL"))
    )
    (comp (ref "R16")
      (value "1M")
      (footprint "R0805")
      (description "RES SMD 1M OHM 1% 1/8W 0805")
      (fields
        (field (name "MANUFACTURER") "Yageo")
        (field (name "MANUFACTURER PART NUMBER") "RC0805FR-071ML")
        (field (name ".CREATOR") "MM")
        (field (name ".CHECKED PCB") "RF")
        (field (name ".CHECKED SCH") "RF")
      )
      (libsource (lib "Integrated_Library_FEDEVEL_APR_2015") (part "RC0805FR-071ML"))
    )
    (comp (ref "R17")
      (value "560R")
      (footprint "R0805")
      (description "RES SMD 560 OHM 1% 1/8W 0805")
      (fields
        (field (name "MANUFACTURER") "Yageo")
        (field (name "MANUFACTURER PART NUMBER") "RC0805FR-07560RL")
        (field (name ".CREATOR") "MM")
        (field (name ".CHECKED PCB") "RF")
        (field (name ".CHECKED SCH") "RF")
      )
      (libsource (lib "Integrated_Library_FEDEVEL_APR_2015") (part "RC0805FR-07560RL"))
    )
    (comp (ref "R18")
      (value "10k")
      (footprint "R0805")
      (description "RES SMD 10K OHM 1% 1/8W 0805")
      (fields
        (field (name "MANUFACTURER") "Yageo")
        (field (name "MANUFACTURER PART NUMBER") "RC0805FR-0710KL")
        (field (name ".CREATOR") "MM")
        (field (name ".CHECKED PCB") "RF")
        (field (name ".CHECKED SCH") "RF")
      )
      (libsource (lib "Integrated_Library_FEDEVEL_APR_2015") (part "RC0805FR-0710KL"))
    )
    (comp (ref "R19")
      (value "10k")
      (footprint "R0805")
      (description "RES SMD 10K OHM 1% 1/8W 0805")
      (fields
        (field (name "MANUFACTURER") "Yageo")
        (field (name "MANUFACTURER PART NUMBER") "RC0805FR-0710KL")
        (field (name ".CREATOR") "MM")
        (field (name ".CHECKED PCB") "RF")
        (field (name ".CHECKED SCH") "RF")
      )
      (libsource (lib "Integrated_Library_FEDEVEL_APR_2015") (part "RC0805FR-0710KL"))
    )
    (comp (ref "R20")
      (value "10k")
      (footprint "R0805")
      (description "RES SMD 10K OHM 1% 1/8W 0805")
      (fields
        (field (name "MANUFACTURER") "Yageo")
        (field (name "MANUFACTURER PART NUMBER") "RC0805FR-0710KL")
        (field (name ".CREATOR") "MM")
        (field (name ".CHECKED PCB") "RF")
        (field (name ".CHECKED SCH") "RF")
      )
      (libsource (lib "Integrated_Library_FEDEVEL_APR_2015") (part "RC0805FR-0710KL"))
    )
    (comp (ref "R21")
      (value "10k")
      (footprint "R0805")
      (description "RES SMD 10K OHM 1% 1/8W 0805")
      (fields
        (field (name "MANUFACTURER") "Yageo")
        (field (name "MANUFACTURER PART NUMBER") "RC0805FR-0710KL")
        (field (name ".CREATOR") "MM")
        (field (name ".CHECKED PCB") "RF")
        (field (name ".CHECKED SCH") "RF")
      )
      (libsource (lib "Integrated_Library_FEDEVEL_APR_2015") (part "RC0805FR-0710KL"))
    )
    (comp (ref "R22")
      (value "560R")
      (footprint "R0805")
      (description "RES SMD 560 OHM 1% 1/8W 0805")
      (fields
        (field (name "MANUFACTURER") "Yageo")
        (field (name "MANUFACTURER PART NUMBER") "RC0805FR-07560RL")
        (field (name ".CREATOR") "MM")
        (field (name ".CHECKED PCB") "RF")
        (field (name ".CHECKED SCH") "RF")
      )
      (libsource (lib "Integrated_Library_FEDEVEL_APR_2015") (part "RC0805FR-07560RL"))
    )
    (comp (ref "R23")
      (value "22R")
      (footprint "R0805")
      (description "RES SMD 22 OHM 1% 1/8W 0805")
      (fields
        (field (name "MANUFACTURER") "Yageo")
        (field (name "MANUFACTURER PART NUMBER") "RC0805FR-0722RL")
        (field (name ".CREATOR") "MM")
        (field (name ".CHECKED PCB") "RF")
        (field (name ".CHECKED SCH") "RF")
      )
      (libsource (lib "Integrated_Library_FEDEVEL_APR_2015") (part "RC0805FR-0722RL"))
    )
    (comp (ref "R24")
      (value "22R")
      (footprint "R0805")
      (description "RES SMD 22 OHM 1% 1/8W 0805")
      (fields
        (field (name "MANUFACTURER") "Yageo")
        (field (name "MANUFACTURER PART NUMBER") "RC0805FR-0722RL")
        (field (name ".CREATOR") "MM")
        (field (name ".CHECKED PCB") "RF")
        (field (name ".CHECKED SCH") "RF")
      )
      (libsource (lib "Integrated_Library_FEDEVEL_APR_2015") (part "RC0805FR-0722RL"))
    )
    (comp (ref "R25")
      (value "22R")
      (footprint "R0805")
      (description "RES SMD 22 OHM 1% 1/8W 0805")
      (fields
        (field (name "MANUFACTURER") "Yageo")
        (field (name "MANUFACTURER PART NUMBER") "RC0805FR-0722RL")
        (field (name ".CREATOR") "MM")
        (field (name ".CHECKED PCB") "RF")
        (field (name ".CHECKED SCH") "RF")
      )
      (libsource (lib "Integrated_Library_FEDEVEL_APR_2015") (part "RC0805FR-0722RL"))
    )
    (comp (ref "R26")
      (value "0R")
      (footprint "R0805")
      (description "RES 0.0 OHM 1/8W 0805 SMD")
      (fields
        (field (name "MANUFACTURER") "Yageo")
        (field (name "MANUFACTURER PART NUMBER") "RC0805JR-070RL")
        (field (name ".CHECKED PCB") "RF")
        (field (name ".CHECKED SCH") "RF")
      )
      (libsource (lib "Integrated_Library_FEDEVEL_APR_2015") (part "RC0805JR-070RL"))
    )
    (comp (ref "R27")
      (value "0R")
      (footprint "R0805")
      (description "RES 0.0 OHM 1/8W 0805 SMD")
      (fields
        (field (name "MANUFACTURER") "Yageo")
        (field (name "MANUFACTURER PART NUMBER") "RC0805JR-070RL")
        (field (name ".CHECKED PCB") "RF")
        (field (name ".CHECKED SCH") "RF")
      )
      (libsource (lib "Integrated_Library_FEDEVEL_APR_2015") (part "RC0805JR-070RL"))
    )
    (comp (ref "R28")
      (value "0R")
      (footprint "R0805")
      (description "RES 0.0 OHM 1/8W 0805 SMD")
      (fields
        (field (name "MANUFACTURER") "Yageo")
        (field (name "MANUFACTURER PART NUMBER") "RC0805JR-070RL")
        (field (name ".CHECKED PCB") "RF")
        (field (name ".CHECKED SCH") "RF")
      )
      (libsource (lib "Integrated_Library_FEDEVEL_APR_2015") (part "RC0805JR-070RL"))
    )
    (comp (ref "SCKT FOR U1")
      (value "28-DIP Socket")
      (footprint "28_DIP_7.62mm_SOCKET")
      (description "CONN IC DIP SOCKET 28POS TIN")
      (fields
        (field (name "MANUFACTURER") "3M")
        (field (name "MANUFACTURER PART NUMBER") "4828-3004-CP")
        (field (name ".CREATOR") "MM")
        (field (name ".CHECKED PCB") "RF")
        (field (name ".CHECKED SCH") "RF")
      )
      (libsource (lib "Integrated_Library_FEDEVEL_APR_2015") (part "4828-3004-CP"))
    )
    (comp (ref "SW1")
      (value "1825910-6")
      (footprint "1825910-6")
      (description "SWITCH TACTILE SPST-NO 0.05A 24V")
      (fields
        (field (name "MANUFACTURER") "TE Connectivity")
        (field (name ".CREATOR") "MM")
        (field (name ".CHECKED PCB") "RF")
        (field (name ".CHECKED SCH") "RF")
      )
      (libsource (lib "Integrated_Library_FEDEVEL_APR_2015") (part "1825910-6"))
    )
    (comp (ref "SW2")
      (value "1825910-6")
      (footprint "1825910-6")
      (description "SWITCH TACTILE SPST-NO 0.05A 24V")
      (fields
        (field (name "MANUFACTURER") "TE Connectivity")
        (field (name ".CREATOR") "MM")
        (field (name ".CHECKED PCB") "RF")
        (field (name ".CHECKED SCH") "RF")
      )
      (libsource (lib "Integrated_Library_FEDEVEL_APR_2015") (part "1825910-6"))
    )
    (comp (ref "U1")
      (value "ATMEGA328P-PU")
      (footprint "28_DIP_7.62mm")
      (description "IC MCU 8BIT 32KB FLASH 28DIP")
      (fields
        (field (name "MANUFACTURER") "Atmel")
        (field (name ".CREATOR") "MM")
        (field (name ".CHECKED PCB") "RF")
        (field (name ".CHECKED SCH") "RF")
      )
      (libsource (lib "Integrated_Library_FEDEVEL_APR_2015") (part "ATMEGA328P-PU"))
    )
    (comp (ref "U2")
      (value "ATMEGA16U2-AU")
      (footprint "TQFP32")
      (description "IC MCU 8BIT 16KB FLASH 32TQFP")
      (fields
        (field (name "MANUFACTURER") "Atmel")
        (field (name ".CREATOR") "MM")
        (field (name ".CHECKED PCB") "RF")
        (field (name ".CHECKED SCH") "RF")
      )
      (libsource (lib "Integrated_Library_FEDEVEL_APR_2015") (part "ATMEGA16U2-AU"))
    )
    (comp (ref "U3")
      (value "TL1963A-33DCQR")
      (footprint "DCQ (R-PDSO-G6)")
      (description "IC REG LDO 3.3V 1.5A SOT223-6")
      (fields
        (field (name "MANUFACTURER") "Texas Instruments")
        (field (name ".CREATOR") "MM")
        (field (name ".CHECKED PCB") "RF")
        (field (name ".CHECKED SCH") "RF")
      )
      (libsource (lib "Integrated_Library_FEDEVEL_APR_2015") (part "TL1963A-33DCQR"))
    )
    (comp (ref "U4")
      (value "SN74AHC1G09DBVR")
      (footprint "DBV_SOT_23_5")
      (description "IC GATE AND SGL 2INP SOT23-5")
      (fields (field (name "MANUFACTURER") "Texas Instruments") (field (name ".CREATOR") "MM"))
      (libsource (lib "Integrated_Library_FEDEVEL_APR_2015") (part "SN74AHC1G09DBVR"))
    )
    (comp (ref "U5")
      (value "SN74AHC1G09DBVR")
      (footprint "DBV_SOT_23_5")
      (description "IC GATE AND SGL 2INP SOT23-5")
      (fields (field (name "MANUFACTURER") "Texas Instruments") (field (name ".CREATOR") "MM"))
      (libsource (lib "Integrated_Library_FEDEVEL_APR_2015") (part "SN74AHC1G09DBVR"))
    )
    (comp (ref "U6")
      (value "SN74AHC1G09DBVR")
      (footprint "DBV_SOT_23_5")
      (description "IC GATE AND SGL 2INP SOT23-5")
      (fields (field (name "MANUFACTURER") "Texas Instruments") (field (name ".CREATOR") "MM"))
      (libsource (lib "Integrated_Library_FEDEVEL_APR_2015") (part "SN74AHC1G09DBVR"))
    )
    (comp (ref "U7")
      (value "SN74AHC1G09DBVR")
      (footprint "DBV_SOT_23_5")
      (description "IC GATE AND SGL 2INP SOT23-5")
      (fields (field (name "MANUFACTURER") "Texas Instruments") (field (name ".CREATOR") "MM"))
      (libsource (lib "Integrated_Library_FEDEVEL_APR_2015") (part "SN74AHC1G09DBVR"))
    )
    (comp (ref "Y1")
      (value "ABM7-16.000MHZ-D2Y-T")
      (footprint "ABM7_v1_1_BIG")
      (description "CRYSTAL 16MHZ 18PF SMD")
      (fields
        (field (name "MANUFACTURER") "Abracon LLC")
        (field (name ".CREATOR") "MM")
        (field (name ".CHECKED PCB") "RF")
        (field (name ".CHECKED SCH") "RF")
      )
      (libsource (lib "Integrated_Library_FEDEVEL_APR_2015") (part "ABM7-16.000MHZ-D2Y-T"))
    )
    (comp (ref "Y2")
      (value "ABM7-16.000MHZ-D2Y-T")
      (footprint "ABM7_v1_1_BIG")
      (description "CRYSTAL 16MHZ 18PF SMD")
      (fields
        (field (name "MANUFACTURER") "Abracon LLC")
        (field (name ".CREATOR") "MM")
        (field (name ".CHECKED PCB") "RF")
        (field (name ".CHECKED SCH") "RF")
      )
      (libsource (lib "Integrated_Library_FEDEVEL_APR_2015") (part "ABM7-16.000MHZ-D2Y-T"))
    )
    (comp (ref "Z1")
      (value "CG0603MLC-05E")
      (footprint "R0603")
      (description "VARISTOR 0603")
      (fields
        (field (name "MANUFACTURER") "Bourns Inc.")
        (field (name ".CREATOR") "MM")
        (field (name ".CHECKED PCB") "RF")
        (field (name ".CHECKED SCH") "RF")
      )
      (libsource (lib "Integrated_Library_FEDEVEL_APR_2015") (part "CG0603MLC-05E"))
    )
    (comp (ref "Z2")
      (value "CG0603MLC-05E")
      (footprint "R0603")
      (description "VARISTOR 0603")
      (fields
        (field (name "MANUFACTURER") "Bourns Inc.")
        (field (name ".CREATOR") "MM")
        (field (name ".CHECKED PCB") "RF")
        (field (name ".CHECKED SCH") "RF")
      )
      (libsource (lib "Integrated_Library_FEDEVEL_APR_2015") (part "CG0603MLC-05E"))
    )
  )
  (nets
    (net (code "1") (name "+3V3") (class "Default")
      (node (ref "C13") (pin "1") (pinfunction "1_1") (pintype "passive"))
      (node (ref "C16") (pin "1") (pinfunction "1_1") (pintype "passive"))
      (node (ref "J1") (pin "4") (pinfunction "4_4") (pintype "passive"))
      (node (ref "JP4") (pin "3") (pinfunction "3_3") (pintype "passive"))
      (node (ref "R28") (pin "1") (pinfunction "1_1") (pintype "passive"))
      (node (ref "U3") (pin "4") (pinfunction "OUT_4") (pintype "passive"))
      (node (ref "U3") (pin "5") (pinfunction "SENSE_5") (pintype "passive"))
    )
    (net (code "2") (name "+5V") (class "Default")
      (node (ref "C12") (pin "1") (pinfunction "1_1") (pintype "passive"))
      (node (ref "C14") (pin "1") (pinfunction "1_1") (pintype "passive"))
      (node (ref "C2") (pin "1") (pinfunction "1_1") (pintype "passive"))
      (node (ref "C6") (pin "1") (pinfunction "1_1") (pintype "passive"))
      (node (ref "J1") (pin "5") (pinfunction "5_5") (pintype "passive"))
      (node (ref "J8") (pin "1") (pinfunction "1_1") (pintype "passive"))
      (node (ref "JP4") (pin "1") (pinfunction "1_1") (pintype "passive"))
      (node (ref "L1") (pin "2") (pinfunction "2_2") (pintype "passive"))
      (node (ref "R27") (pin "2") (pinfunction "2_2") (pintype "passive"))
      (node (ref "U2") (pin "31") (pinfunction "UVCC_31") (pintype "passive"))
      (node (ref "U3") (pin "1") (pinfunction "~{SHDN}_1") (pintype "passive"))
      (node (ref "U3") (pin "2") (pinfunction "IN_2") (pintype "passive"))
    )
    (net (code "3") (name "+5V{slash}3V3") (class "Default")
      (node (ref "C15") (pin "1") (pinfunction "1_1") (pintype "passive"))
      (node (ref "C17") (pin "1") (pinfunction "1_1") (pintype "passive"))
      (node (ref "C26") (pin "1") (pinfunction "1_1") (pintype "passive"))
      (node (ref "C28") (pin "1") (pinfunction "1_1") (pintype "passive"))
      (node (ref "C29") (pin "1") (pinfunction "1_1") (pintype "passive"))
      (node (ref "C30") (pin "1") (pinfunction "1_1") (pintype "passive"))
      (node (ref "C34") (pin "1") (pinfunction "1_1") (pintype "passive"))
      (node (ref "C8") (pin "1") (pinfunction "1_1") (pintype "passive"))
      (node (ref "D5") (pin "1") (pinfunction "Cathode_1") (pintype "passive"))
      (node (ref "D6") (pin "1") (pinfunction "Cathode_1") (pintype "passive"))
      (node (ref "FB1") (pin "1") (pinfunction "1_1") (pintype "passive"))
      (node (ref "FB2") (pin "1") (pinfunction "1_1") (pintype "passive"))
      (node (ref "FB3") (pin "1") (pinfunction "1_1") (pintype "passive"))
      (node (ref "J1") (pin "2") (pinfunction "2_2") (pintype "passive"))
      (node (ref "J5") (pin "2") (pinfunction "2_2") (pintype "passive"))
      (node (ref "J6") (pin "2") (pinfunction "2_2") (pintype "passive"))
      (node (ref "JP4") (pin "2") (pinfunction "2_2") (pintype "passive"))
      (node (ref "R1") (pin "2") (pinfunction "2_2") (pintype "passive"))
      (node (ref "R14") (pin "2") (pinfunction "2_2") (pintype "passive"))
      (node (ref "R15") (pin "2") (pinfunction "2_2") (pintype "passive"))
      (node (ref "R17") (pin "2") (pinfunction "2_2") (pintype "passive"))
      (node (ref "R18") (pin "2") (pinfunction "2_2") (pintype "passive"))
      (node (ref "R19") (pin "2") (pinfunction "2_2") (pintype "passive"))
      (node (ref "R2") (pin "2") (pinfunction "2_2") (pintype "passive"))
      (node (ref "R20") (pin "2") (pinfunction "2_2") (pintype "passive"))
      (node (ref "R21") (pin "2") (pinfunction "2_2") (pintype "passive"))
      (node (ref "R27") (pin "1") (pinfunction "1_1") (pintype "passive"))
      (node (ref "R28") (pin "2") (pinfunction "2_2") (pintype "passive"))
      (node (ref "R3") (pin "2") (pinfunction "2_2") (pintype "passive"))
      (node (ref "R4") (pin "2") (pinfunction "2_2") (pintype "passive"))
      (node (ref "U4") (pin "5") (pinfunction "VCC_5") (pintype "power_in"))
      (node (ref "U5") (pin "5") (pinfunction "VCC_5") (pintype "power_in"))
      (node (ref "U6") (pin "5") (pinfunction "VCC_5") (pintype "power_in"))
      (node (ref "U7") (pin "5") (pinfunction "VCC_5") (pintype "power_in"))
    )
    (net (code "4") (name "+AREF") (class "Default")
      (node (ref "C21") (pin "1") (pinfunction "1_1") (pintype "passive"))
      (node (ref "C24") (pin "1") (pinfunction "1_1") (pintype "passive"))
      (node (ref "J4") (pin "8") (pinfunction "8_8") (pintype "passive"))
      (node (ref "U1") (pin "21") (pinfunction "AREF_21") (pintype "passive"))
    )
    (net (code "5") (name "/+3V3_16U2_UCAP") (class "Default")
      (node (ref "C7") (pin "2") (pinfunction "2_2") (pintype "passive"))
      (node (ref "R26") (pin "1") (pinfunction "1_1") (pintype "passive"))
      (node (ref "U2") (pin "27") (pinfunction "UCAP_27") (pintype "passive"))
    )
    (net (code "6") (name "/+5V_USB") (class "Default")
      (node (ref "C1") (pin "1") (pinfunction "1_1") (pintype "passive"))
      (node (ref "J7") (pin "1") (pinfunction "P1_1") (pintype "passive"))
      (node (ref "L1") (pin "1") (pinfunction "1_1") (pintype "passive"))
    )
    (net (code "7") (name "/+5V{slash}3V3_16U2") (class "Default")
      (node (ref "C3") (pin "1") (pinfunction "1_1") (pintype "passive"))
      (node (ref "C4") (pin "1") (pinfunction "1_1") (pintype "passive"))
      (node (ref "C5") (pin "1") (pinfunction "1_1") (pintype "passive"))
      (node (ref "FB1") (pin "2") (pinfunction "2_2") (pintype "passive"))
      (node (ref "R26") (pin "2") (pinfunction "2_2") (pintype "passive"))
      (node (ref "U2") (pin "32") (pinfunction "AVCC_32") (pintype "passive"))
      (node (ref "U2") (pin "4") (pinfunction "VCC_4") (pintype "passive"))
    )
    (net (code "8") (name "/+5V{slash}3V3_328P_AVCC") (class "Default")
      (node (ref "C22") (pin "1") (pinfunction "1_1") (pintype "passive"))
      (node (ref "C23") (pin "1") (pinfunction "1_1") (pintype "passive"))
      (node (ref "FB3") (pin "2") (pinfunction "2_2") (pintype "passive"))
      (node (ref "U1") (pin "20") (pinfunction "AVCC_20") (pintype "passive"))
    )
    (net (code "9") (name "/+5V{slash}3V3_328P_VCC") (class "Default")
      (node (ref "C19") (pin "1") (pinfunction "1_1") (pintype "passive"))
      (node (ref "C20") (pin "1") (pinfunction "1_1") (pintype "passive"))
      (node (ref "FB2") (pin "2") (pinfunction "2_2") (pintype "passive"))
      (node (ref "U1") (pin "7") (pinfunction "VCC_7") (pintype "passive"))
    )
    (net (code "10") (name "/16U2PROG_328P_RESETn") (class "Default")
      (node (ref "JP1") (pin "2") (pinfunction "2_2") (pintype "passive"))
      (node (ref "R1") (pin "1") (pinfunction "1_1") (pintype "passive"))
      (node (ref "U2") (pin "13") (pinfunction "~{CTS}_/~{_HWB}_/_T0_/_AIN6_/_INT7_/_PD7_13") (pintype "passive"))
    )
    (net (code "11") (name "/16U2_16MHZ_XTAL1") (class "Default")
      (node (ref "C10") (pin "2") (pinfunction "2_2") (pintype "passive"))
      (node (ref "R9") (pin "1") (pinfunction "1_1") (pintype "passive"))
      (node (ref "U2") (pin "1") (pinfunction "XTAL1_1") (pintype "passive"))
      (node (ref "Y2") (pin "1") (pinfunction "1_1") (pintype "passive"))
    )
    (net (code "12") (name "/16U2_16MHZ_XTAL2") (class "Default")
      (node (ref "C9") (pin "2") (pinfunction "2_2") (pintype "passive"))
      (node (ref "R9") (pin "2") (pinfunction "2_2") (pintype "passive"))
      (node (ref "U2") (pin "2") (pinfunction "XTAL2_/_PC0_2") (pintype "passive"))
      (node (ref "Y2") (pin "2") (pinfunction "2_2") (pintype "passive"))
    )
    (net (code "13") (name "/16U2_BUF_RESETn") (class "Default")
      (node (ref "C31") (pin "1") (pinfunction "1_1") (pintype "passive"))
      (node (ref "R23") (pin "2") (pinfunction "2_2") (pintype "passive"))
      (node (ref "U5") (pin "1") (pinfunction "A_1") (pintype "passive"))
      (node (ref "U5") (pin "2") (pinfunction "B_2") (pintype "passive"))
    )
    (net (code "14") (name "/16U2_HDR_RESETn") (class "Default")
      (node (ref "J6") (pin "5") (pinfunction "5_5") (pintype "passive"))
      (node (ref "JP3") (pin "3") (pinfunction "3_3") (pintype "passive"))
    )
    (net (code "15") (name "/16U2_MISO") (class "Default")
      (node (ref "J6") (pin "1") (pinfunction "1_1") (pintype "passive"))
      (node (ref "U2") (pin "17") (pinfunction "PDO_/_MISO_/_PCINT3_/_PB3_17") (pintype "passive"))
    )
    (net (code "16") (name "/16U2_MOSI") (class "Default")
      (node (ref "J6") (pin "4") (pinfunction "4_4") (pintype "passive"))
      (node (ref "U2") (pin "16") (pinfunction "PDI_/_MOSI_/_PCINT2_/_PB2_16") (pintype "passive"))
    )
    (net (code "17") (name "/16U2_PB4") (class "Default")
      (node (ref "JP2") (pin "1") (pinfunction "1_1") (pintype "passive"))
      (node (ref "JP3") (pin "2") (pinfunction "2_2") (pintype "passive"))
      (node (ref "U2") (pin "18") (pinfunction "T1_/_PCINT4_/_PB4_18") (pintype "passive"))
    )
    (net (code "18") (name "/16U2_PB5") (class "Default")
      (node (ref "JP2") (pin "3") (pinfunction "3_3") (pintype "passive"))
      (node (ref "U2") (pin "19") (pinfunction "PCINT5_/_PB5_19") (pintype "passive"))
    )
    (net (code "19") (name "/16U2_PB6") (class "Default")
      (node (ref "JP2") (pin "2") (pinfunction "2_2") (pintype "passive"))
      (node (ref "U2") (pin "20") (pinfunction "PCINT6_/_PB6_20") (pintype "passive"))
    )
    (net (code "20") (name "/16U2_PB7") (class "Default")
      (node (ref "JP2") (pin "4") (pinfunction "4_4") (pintype "passive"))
      (node (ref "U2") (pin "21") (pinfunction "OC.0A_/_OC.1C_/_PCINT7_/_PB7_21") (pintype "passive"))
    )
    (net (code "21") (name "/16U2_RESETn") (class "Default")
      (node (ref "JP3") (pin "4") (pinfunction "4_4") (pintype "passive"))
      (node (ref "R4") (pin "1") (pinfunction "1_1") (pintype "passive"))
      (node (ref "U2") (pin "24") (pinfunction "PC1_/~{_RESET}_/_DW_24") (pintype "passive"))
      (node (ref "U5") (pin "4") (pinfunction "Y_4") (pintype "passive"))
    )
    (net (code "22") (name "/16U2_RXD") (class "Default")
      (node (ref "R11") (pin "1") (pinfunction "1_1") (pintype "passive"))
      (node (ref "U2") (pin "8") (pinfunction "RXD1_/_AIN1_/_INT2_/_PD2_8") (pintype "passive"))
    )
    (net (code "23") (name "/16U2_RX_LED") (class "Default")
      (node (ref "D4") (pin "1") (pinfunction "cathode_1") (pintype "passive"))
      (node (ref "U2") (pin "10") (pinfunction "AIN3_/_INT5_/_PD4_10") (pintype "passive"))
    )
    (net (code "24") (name "/16U2_SCLK") (class "Default")
      (node (ref "J6") (pin "3") (pinfunction "3_3") (pintype "passive"))
      (node (ref "R5") (pin "2") (pinfunction "2_2") (pintype "passive"))
    )
    (net (code "25") (name "/16U2_SCLK_R") (class "Default")
      (node (ref "R5") (pin "1") (pinfunction "1_1") (pintype "passive"))
      (node (ref "U2") (pin "15") (pinfunction "SCLK_/_PCINT1_/_PB1_15") (pintype "passive"))
    )
    (net (code "26") (name "/16U2_TXD") (class "Default")
      (node (ref "R10") (pin "1") (pinfunction "1_1") (pintype "passive"))
      (node (ref "U2") (pin "9") (pinfunction "TXD1_/_INT3_/_PD3_9") (pintype "passive"))
    )
    (net (code "27") (name "/16U2_TX_LED") (class "Default")
      (node (ref "D3") (pin "1") (pinfunction "cathode_1") (pintype "passive"))
      (node (ref "U2") (pin "11") (pinfunction "XCK_/_AIN4_/_PCINT12_/_PD5_11") (pintype "passive"))
    )
    (net (code "28") (name "/328P_16MHZ_XTAL1") (class "Default")
      (node (ref "C27") (pin "2") (pinfunction "2_2") (pintype "passive"))
      (node (ref "R16") (pin "1") (pinfunction "1_1") (pintype "passive"))
      (node (ref "U1") (pin "9") (pinfunction "PB6_/_PCINT6_/_TOSC1_/_XTAL1_9") (pintype "passive"))
      (node (ref "Y1") (pin "1") (pinfunction "1_1") (pintype "passive"))
    )
    (net (code "29") (name "/328P_16MHZ_XTAL2") (class "Default")
      (node (ref "C25") (pin "2") (pinfunction "2_2") (pintype "passive"))
      (node (ref "R16") (pin "2") (pinfunction "2_2") (pintype "passive"))
      (node (ref "U1") (pin "10") (pinfunction "PB7_/_PCINT7_/_TOSC2_/_XTAL2_10") (pintype "passive"))
      (node (ref "Y1") (pin "2") (pinfunction "2_2") (pintype "passive"))
    )
    (net (code "30") (name "/328P_AUTORESETn") (class "Default")
      (node (ref "C11") (pin "1") (pinfunction "1_1") (pintype "passive"))
      (node (ref "R18") (pin "1") (pinfunction "1_1") (pintype "passive"))
      (node (ref "U6") (pin "1") (pinfunction "A_1") (pintype "passive"))
    )
    (net (code "31") (name "/328P_BUF_RESETn") (class "Default")
      (node (ref "C32") (pin "1") (pinfunction "1_1") (pintype "passive"))
      (node (ref "R24") (pin "2") (pinfunction "2_2") (pintype "passive"))
      (node (ref "U6") (pin "2") (pinfunction "B_2") (pintype "passive"))
    )
    (net (code "32") (name "/328P_RESETn") (class "Default")
      (node (ref "J1") (pin "3") (pinfunction "3_3") (pintype "passive"))
      (node (ref "J5") (pin "5") (pinfunction "5_5") (pintype "passive"))
      (node (ref "JP3") (pin "1") (pinfunction "1_1") (pintype "passive"))
      (node (ref "R14") (pin "1") (pinfunction "1_1") (pintype "passive"))
      (node (ref "U1") (pin "1") (pinfunction "PC6_/_PCINT14_/~{_RESET}_1") (pintype "passive"))
      (node (ref "U6") (pin "4") (pinfunction "Y_4") (pintype "passive"))
    )
    (net (code "33") (name "/AD0") (class "Default")
      (node (ref "J2") (pin "1") (pinfunction "1_1") (pintype "passive"))
      (node (ref "U1") (pin "23") (pinfunction "PCINT8_/_ADC0_/_PC0_23") (pintype "passive"))
    )
    (net (code "34") (name "/AD1") (class "Default")
      (node (ref "J2") (pin "2") (pinfunction "2_2") (pintype "passive"))
      (node (ref "U1") (pin "24") (pinfunction "PCINT9_/_ADC1_/_PC1_24") (pintype "passive"))
    )
    (net (code "35") (name "/AD2") (class "Default")
      (node (ref "J2") (pin "3") (pinfunction "3_3") (pintype "passive"))
      (node (ref "U1") (pin "25") (pinfunction "PCINT10_/_ADC2_/_PC2_25") (pintype "passive"))
    )
    (net (code "36") (name "/AD3") (class "Default")
      (node (ref "J2") (pin "4") (pinfunction "4_4") (pintype "passive"))
      (node (ref "U1") (pin "26") (pinfunction "PCINT11_/_ADC3_/_PC3_26") (pintype "passive"))
    )
    (net (code "37") (name "/AD4{slash}SDA") (class "Default")
      (node (ref "J2") (pin "5") (pinfunction "5_5") (pintype "passive"))
      (node (ref "J4") (pin "9") (pinfunction "9_9") (pintype "passive"))
      (node (ref "U1") (pin "27") (pinfunction "SDA_/_PCINT12_/_ADC4_/_PC4_27") (pintype "passive"))
    )
    (net (code "38") (name "/AD5{slash}SCL") (class "Default")
      (node (ref "J2") (pin "6") (pinfunction "6_6") (pintype "passive"))
      (node (ref "J4") (pin "10") (pinfunction "10_10") (pintype "passive"))
      (node (ref "U1") (pin "28") (pinfunction "SCL_/_PCINT13_/_ADC5_/_PC5_28") (pintype "passive"))
    )
    (net (code "39") (name "/BUTTON_RESETn") (class "Default")
      (node (ref "D6") (pin "2") (pinfunction "Anode_2") (pintype "passive"))
      (node (ref "R20") (pin "1") (pinfunction "1_1") (pintype "passive"))
      (node (ref "R24") (pin "1") (pinfunction "1_1") (pintype "passive"))
      (node (ref "SW1") (pin "1") (pinfunction "1_1") (pintype "passive"))
      (node (ref "SW1") (pin "2") (pinfunction "2_2") (pintype "passive"))
    )
    (net (code "40") (name "/CON_USB_N") (class "Default")
      (node (ref "J7") (pin "2") (pinfunction "P2_2") (pintype "passive"))
      (node (ref "R6") (pin "1") (pinfunction "1_1") (pintype "passive"))
      (node (ref "Z1") (pin "2") (pinfunction "2_2") (pintype "passive"))
    )
    (net (code "41") (name "/CON_USB_P") (class "Default")
      (node (ref "J7") (pin "3") (pinfunction "P3_3") (pintype "passive"))
      (node (ref "R7") (pin "1") (pinfunction "1_1") (pintype "passive"))
      (node (ref "Z2") (pin "2") (pinfunction "2_2") (pintype "passive"))
    )
    (net (code "42") (name "/IO0") (class "Default")
      (node (ref "J3") (pin "1") (pinfunction "1_1") (pintype "passive"))
      (node (ref "R10") (pin "2") (pinfunction "2_2") (pintype "passive"))
      (node (ref "U1") (pin "2") (pinfunction "RXD_/_PCINT16_/_PD0_2") (pintype "passive"))
    )
    (net (code "43") (name "/IO1") (class "Default")
      (node (ref "J3") (pin "2") (pinfunction "2_2") (pintype "passive"))
      (node (ref "R11") (pin "2") (pinfunction "2_2") (pintype "passive"))
      (node (ref "U1") (pin "3") (pinfunction "TXD_/_PCINT17_/_PD1_3") (pintype "passive"))
    )
    (net (code "44") (name "/IO2") (class "Default")
      (node (ref "J3") (pin "3") (pinfunction "3_3") (pintype "passive"))
      (node (ref "U1") (pin "4") (pinfunction "INT0_/_PCINT18_/_PD2_4") (pintype "passive"))
    )
    (net (code "45") (name "/IO3") (class "Default")
      (node (ref "J3") (pin "4") (pinfunction "4_4") (pintype "passive"))
      (node (ref "U1") (pin "5") (pinfunction "OC2B_/_INT1_/_PCINT19_/_PD3_5") (pintype "passive"))
    )
    (net (code "46") (name "/IO4") (class "Default")
      (node (ref "J3") (pin "5") (pinfunction "5_5") (pintype "passive"))
      (node (ref "U1") (pin "6") (pinfunction "XCK_/_T0_/_PCINT20_/_PD4_6") (pintype "passive"))
    )
    (net (code "47") (name "/IO5") (class "Default")
      (node (ref "J3") (pin "6") (pinfunction "6_6") (pintype "passive"))
      (node (ref "U1") (pin "11") (pinfunction "OC0B_/_T1_/_PCINT21_/_PD5_11") (pintype "passive"))
    )
    (net (code "48") (name "/IO6") (class "Default")
      (node (ref "J3") (pin "7") (pinfunction "7_7") (pintype "passive"))
      (node (ref "U1") (pin "12") (pinfunction "OC0A_/_AIN0_/_PCINT22_/_PD6_12") (pintype "passive"))
    )
    (net (code "49") (name "/IO7") (class "Default")
      (node (ref "J3") (pin "8") (pinfunction "8_8") (pintype "passive"))
      (node (ref "U1") (pin "13") (pinfunction "AIN1_/_PCINT23_/_PD7_13") (pintype "passive"))
    )
    (net (code "50") (name "/IO8") (class "Default")
      (node (ref "J4") (pin "1") (pinfunction "1_1") (pintype "passive"))
      (node (ref "R22") (pin "1") (pinfunction "1_1") (pintype "passive"))
      (node (ref "U1") (pin "14") (pinfunction "CLKO_/_ICP1_/_PCINT0_/_PB0_14") (pintype "passive"))
    )
    (net (code "51") (name "/IO9") (class "Default")
      (node (ref "J4") (pin "2") (pinfunction "2_2") (pintype "passive"))
      (node (ref "U1") (pin "15") (pinfunction "OC1A_/_PCINT1_/_PB1_15") (pintype "passive"))
    )
    (net (code "52") (name "/MISO") (class "Default")
      (node (ref "J4") (pin "5") (pinfunction "5_5") (pintype "passive"))
      (node (ref "J5") (pin "1") (pinfunction "1_1") (pintype "passive"))
      (node (ref "U1") (pin "18") (pinfunction "MISO_/_PCINT4_/_PB4_18") (pintype "passive"))
    )
    (net (code "53") (name "/MOSI") (class "Default")
      (node (ref "J4") (pin "4") (pinfunction "4_4") (pintype "passive"))
      (node (ref "J5") (pin "4") (pinfunction "4_4") (pintype "passive"))
      (node (ref "U1") (pin "17") (pinfunction "MOSI_/_OC2A_/_PCINT3_/_PB3_17") (pintype "passive"))
    )
    (net (code "54") (name "/SCK") (class "Default")
      (node (ref "J4") (pin "6") (pinfunction "6_6") (pintype "passive"))
      (node (ref "J5") (pin "3") (pinfunction "3_3") (pintype "passive"))
      (node (ref "R13") (pin "2") (pinfunction "2_2") (pintype "passive"))
      (node (ref "U4") (pin "1") (pinfunction "A_1") (pintype "passive"))
      (node (ref "U4") (pin "2") (pinfunction "B_2") (pintype "passive"))
    )
    (net (code "55") (name "/SCK_R") (class "Default")
      (node (ref "R13") (pin "1") (pinfunction "1_1") (pintype "passive"))
      (node (ref "U1") (pin "19") (pinfunction "SCK_/_PCINT5_/_PB5_19") (pintype "passive"))
    )
    (net (code "56") (name "/SS") (class "Default")
      (node (ref "J4") (pin "3") (pinfunction "3_3") (pintype "passive"))
      (node (ref "U1") (pin "16") (pinfunction "~{SS}_/_OC1B_/_PCINT2_/_PB2_16") (pintype "passive"))
    )
    (net (code "57") (name "/USB_N") (class "Default")
      (node (ref "R6") (pin "2") (pinfunction "2_2") (pintype "passive"))
      (node (ref "U2") (pin "30") (pinfunction "D-_30") (pintype "passive"))
    )
    (net (code "58") (name "/USB_P") (class "Default")
      (node (ref "R7") (pin "2") (pinfunction "2_2") (pintype "passive"))
      (node (ref "U2") (pin "29") (pinfunction "D+_29") (pintype "passive"))
    )
    (net (code "59") (name "/USER_BUTTON") (class "Default")
      (node (ref "R21") (pin "1") (pinfunction "1_1") (pintype "passive"))
      (node (ref "R25") (pin "1") (pinfunction "1_1") (pintype "passive"))
      (node (ref "SW2") (pin "1") (pinfunction "1_1") (pintype "passive"))
      (node (ref "SW2") (pin "2") (pinfunction "2_2") (pintype "passive"))
    )
    (net (code "60") (name "/USER_BUTTON_BUF") (class "Default")
      (node (ref "C33") (pin "1") (pinfunction "1_1") (pintype "passive"))
      (node (ref "R25") (pin "2") (pinfunction "2_2") (pintype "passive"))
      (node (ref "U7") (pin "1") (pinfunction "A_1") (pintype "passive"))
      (node (ref "U7") (pin "2") (pinfunction "B_2") (pintype "passive"))
    )
    (net (code "61") (name "GND") (class "Default")
      (node (ref "C1") (pin "2") (pinfunction "2_2") (pintype "passive"))
      (node (ref "C10") (pin "1") (pinfunction "1_1") (pintype "passive"))
      (node (ref "C12") (pin "2") (pinfunction "2_2") (pintype "passive"))
      (node (ref "C13") (pin "2") (pinfunction "2_2") (pintype "passive"))
      (node (ref "C14") (pin "2") (pinfunction "2_2") (pintype "passive"))
      (node (ref "C15") (pin "2") (pinfunction "2_2") (pintype "passive"))
      (node (ref "C16") (pin "2") (pinfunction "2_2") (pintype "passive"))
      (node (ref "C17") (pin "2") (pinfunction "2_2") (pintype "passive"))
      (node (ref "C19") (pin "2") (pinfunction "2_2") (pintype "passive"))
      (node (ref "C2") (pin "2") (pinfunction "2_2") (pintype "passive"))
      (node (ref "C20") (pin "2") (pinfunction "2_2") (pintype "passive"))
      (node (ref "C21") (pin "2") (pinfunction "2_2") (pintype "passive"))
      (node (ref "C22") (pin "2") (pinfunction "2_2") (pintype "passive"))
      (node (ref "C23") (pin "2") (pinfunction "2_2") (pintype "passive"))
      (node (ref "C24") (pin "2") (pinfunction "2_2") (pintype "passive"))
      (node (ref "C25") (pin "1") (pinfunction "1_1") (pintype "passive"))
      (node (ref "C26") (pin "2") (pinfunction "2_2") (pintype "passive"))
      (node (ref "C27") (pin "1") (pinfunction "1_1") (pintype "passive"))
      (node (ref "C28") (pin "2") (pinfunction "2_2") (pintype "passive"))
      (node (ref "C29") (pin "2") (pinfunction "2_2") (pintype "passive"))
      (node (ref "C3") (pin "2") (pinfunction "2_2") (pintype "passive"))
      (node (ref "C30") (pin "2") (pinfunction "2_2") (pintype "passive"))
      (node (ref "C31") (pin "2") (pinfunction "2_2") (pintype "passive"))
      (node (ref "C32") (pin "2") (pinfunction "2_2") (pintype "passive"))
      (node (ref "C33") (pin "2") (pinfunction "2_2") (pintype "passive"))
      (node (ref "C34") (pin "2") (pinfunction "2_2") (pintype "passive"))
      (node (ref "C4") (pin "2") (pinfunction "2_2") (pintype "passive"))
      (node (ref "C5") (pin "2") (pinfunction "2_2") (pintype "passive"))
      (node (ref "C6") (pin "2") (pinfunction "2_2") (pintype "passive"))
      (node (ref "C7") (pin "1") (pinfunction "1_1") (pintype "passive"))
      (node (ref "C8") (pin "2") (pinfunction "2_2") (pintype "passive"))
      (node (ref "C9") (pin "1") (pinfunction "1_1") (pintype "passive"))
      (node (ref "D1") (pin "1") (pinfunction "cathode_1") (pintype "passive"))
      (node (ref "J1") (pin "6") (pinfunction "6_6") (pintype "passive"))
      (node (ref "J1") (pin "7") (pinfunction "7_7") (pintype "passive"))
      (node (ref "J4") (pin "7") (pinfunction "7_7") (pintype "passive"))
      (node (ref "J5") (pin "6") (pinfunction "6_6") (pintype "passive"))
      (node (ref "J6") (pin "6") (pinfunction "6_6") (pintype "passive"))
      (node (ref "J7") (pin "10") (pinfunction "10_10") (pintype "passive"))
      (node (ref "J7") (pin "11") (pinfunction "11_11") (pintype "passive"))
      (node (ref "J7") (pin "5") (pinfunction "P5_5") (pintype "passive"))
      (node (ref "J7") (pin "6") (pinfunction "6_6") (pintype "passive"))
      (node (ref "J7") (pin "7") (pinfunction "7_7") (pintype "passive"))
      (node (ref "J7") (pin "8") (pinfunction "8_8") (pintype "passive"))
      (node (ref "J7") (pin "9") (pinfunction "9_9") (pintype "passive"))
      (node (ref "J9") (pin "1") (pinfunction "1_1") (pintype "passive"))
      (node (ref "MH1") (pin "1") (pinfunction "1_1") (pintype "passive"))
      (node (ref "MH2") (pin "1") (pinfunction "1_1") (pintype "passive"))
      (node (ref "MH3") (pin "1") (pinfunction "1_1") (pintype "passive"))
      (node (ref "R12") (pin "2") (pinfunction "2_2") (pintype "passive"))
      (node (ref "R8") (pin "2") (pinfunction "2_2") (pintype "passive"))
      (node (ref "SW1") (pin "3") (pinfunction "MECH1_3") (pintype "passive"))
      (node (ref "SW1") (pin "4") (pinfunction "MECH2_4") (pintype "passive"))
      (node (ref "SW2") (pin "3") (pinfunction "MECH1_3") (pintype "passive"))
      (node (ref "SW2") (pin "4") (pinfunction "MECH2_4") (pintype "passive"))
      (node (ref "U1") (pin "22") (pinfunction "GND_2_22") (pintype "passive"))
      (node (ref "U1") (pin "8") (pinfunction "GND_1_8") (pintype "passive"))
      (node (ref "U2") (pin "28") (pinfunction "UGND_28") (pintype "passive"))
      (node (ref "U2") (pin "3") (pinfunction "GND_3") (pintype "passive"))
      (node (ref "U3") (pin "3") (pinfunction "GND_3") (pintype "passive"))
      (node (ref "U3") (pin "6") (pinfunction "EPAD_6") (pintype "passive"))
      (node (ref "U4") (pin "3") (pinfunction "GND_3") (pintype "power_in"))
      (node (ref "U5") (pin "3") (pinfunction "GND_3") (pintype "power_in"))
      (node (ref "U6") (pin "3") (pinfunction "GND_3") (pintype "power_in"))
      (node (ref "U7") (pin "3") (pinfunction "GND_3") (pintype "power_in"))
      (node (ref "Z1") (pin "1") (pinfunction "1_1") (pintype "passive"))
      (node (ref "Z2") (pin "1") (pinfunction "1_1") (pintype "passive"))
    )
    (net (code "62") (name "Net-(C11-Pad2)") (class "Default")
      (node (ref "C11") (pin "2") (pinfunction "2_2") (pintype "passive"))
      (node (ref "JP1") (pin "1") (pinfunction "1_1") (pintype "passive"))
    )
    (net (code "63") (name "Net-(D1-ANODE)") (class "Default")
      (node (ref "D1") (pin "2") (pinfunction "ANODE_2") (pintype "passive"))
      (node (ref "R17") (pin "1") (pinfunction "1_1") (pintype "passive"))
    )
    (net (code "64") (name "Net-(D2-ANODE)") (class "Default")
      (node (ref "D2") (pin "2") (pinfunction "ANODE_2") (pintype "passive"))
      (node (ref "R15") (pin "1") (pinfunction "1_1") (pintype "passive"))
    )
    (net (code "65") (name "Net-(D2-cathode)") (class "Default")
      (node (ref "D2") (pin "1") (pinfunction "cathode_1") (pintype "passive"))
      (node (ref "U4") (pin "4") (pinfunction "Y_4") (pintype "passive"))
    )
    (net (code "66") (name "Net-(D3-ANODE)") (class "Default")
      (node (ref "D3") (pin "2") (pinfunction "ANODE_2") (pintype "passive"))
      (node (ref "R2") (pin "1") (pinfunction "1_1") (pintype "passive"))
    )
    (net (code "67") (name "Net-(D4-ANODE)") (class "Default")
      (node (ref "D4") (pin "2") (pinfunction "ANODE_2") (pintype "passive"))
      (node (ref "R3") (pin "1") (pinfunction "1_1") (pintype "passive"))
    )
    (net (code "68") (name "Net-(D5-Anode)") (class "Default")
      (node (ref "D5") (pin "2") (pinfunction "Anode_2") (pintype "passive"))
      (node (ref "R19") (pin "1") (pinfunction "1_1") (pintype "passive"))
      (node (ref "R23") (pin "1") (pinfunction "1_1") (pintype "passive"))
    )
    (net (code "69") (name "Net-(J7-P4)") (class "Default")
      (node (ref "J7") (pin "4") (pinfunction "P4_4") (pintype "passive"))
      (node (ref "R8") (pin "1") (pinfunction "1_1") (pintype "passive"))
    )
    (net (code "70") (name "Net-(JP1-Pad3)") (class "Default")
      (node (ref "JP1") (pin "3") (pinfunction "3_3") (pintype "passive"))
      (node (ref "R12") (pin "1") (pinfunction "1_1") (pintype "passive"))
    )
    (net (code "71") (name "Net-(U7-Y)") (class "Default")
      (node (ref "R22") (pin "2") (pinfunction "2_2") (pintype "passive"))
      (node (ref "U7") (pin "4") (pinfunction "Y_4") (pintype "passive"))
    )
    (net (code "72") (name "unconnected-(J1-Pad1)") (class "Default")
      (node (ref "J1") (pin "1") (pinfunction "1_1") (pintype "passive+no_connect"))
    )
    (net (code "73") (name "unconnected-(J1-Pad8)") (class "Default")
      (node (ref "J1") (pin "8") (pinfunction "8_8") (pintype "passive+no_connect"))
    )
    (net (code "74") (name "unconnected-(MH4-Pad1)") (class "Default")
      (node (ref "MH4") (pin "1") (pinfunction "1_1") (pintype "passive+no_connect"))
    )
    (net (code "75") (name "unconnected-(U2-AIN0_{slash}_INT1_{slash}_PD1-Pad7)") (class "Default")
      (node (ref "U2") (pin "7") (pinfunction "AIN0_/_INT1_/_PD1_7") (pintype "passive+no_connect"))
    )
    (net (code "76") (name "unconnected-(U2-AIN2_{slash}_PCINT11_{slash}_PC2-Pad5)") (class "Default")
      (node (ref "U2") (pin "5") (pinfunction "AIN2_/_PCINT11_/_PC2_5") (pintype "passive+no_connect"))
    )
    (net (code "77") (name "unconnected-(U2-CLKO_{slash}_ICP1_{slash}_INT4_{slash}_PC7-Pad22)") (class "Default")
      (node (ref "U2") (pin "22") (pinfunction "CLKO_/_ICP1_/_INT4_/_PC7_22") (pintype "passive+no_connect"))
    )
    (net (code "78") (name "unconnected-(U2-OC.0B_{slash}_INT0_{slash}_PD0-Pad6)") (class "Default")
      (node (ref "U2") (pin "6") (pinfunction "OC.0B_/_INT0_/_PD0_6") (pintype "passive+no_connect"))
    )
    (net (code "79") (name "unconnected-(U2-OC.1A_{slash}_PCINT8_{slash}_PC6-Pad23)") (class "Default")
      (node (ref "U2") (pin "23") (pinfunction "OC.1A_/_PCINT8_/_PC6_23") (pintype "passive+no_connect"))
    )
    (net (code "80") (name "unconnected-(U2-OC.1B_{slash}_PCINT9_{slash}_PC5-Pad25)") (class "Default")
      (node (ref "U2") (pin "25") (pinfunction "OC.1B_/_PCINT9_/_PC5_25") (pintype "passive+no_connect"))
    )
    (net (code "81") (name "unconnected-(U2-PCINT10_{slash}_PC4-Pad26)") (class "Default")
      (node (ref "U2") (pin "26") (pinfunction "PCINT10_/_PC4_26") (pintype "passive+no_connect"))
    )
    (net (code "82") (name "unconnected-(U2-~{RTS}_{slash}_AIN5_{slash}_INT6_{slash}_PD6-Pad12)") (class "Default")
      (node (ref "U2") (pin "12") (pinfunction "~{RTS}_/_AIN5_/_INT6_/_PD6_12") (pintype "passive"))
    )
    (net (code "83") (name "unconnected-(U2-~{SS}_{slash}_PCINT0_{slash}_PB0-Pad14)") (class "Default")
      (node (ref "U2") (pin "14") (pinfunction "~{SS}_/_PCINT0_/_PB0_14") (pintype "passive+no_connect"))
    )
  )
)
